# board2-d.net
KiCad netlist of a schematic drawn in EAGLE
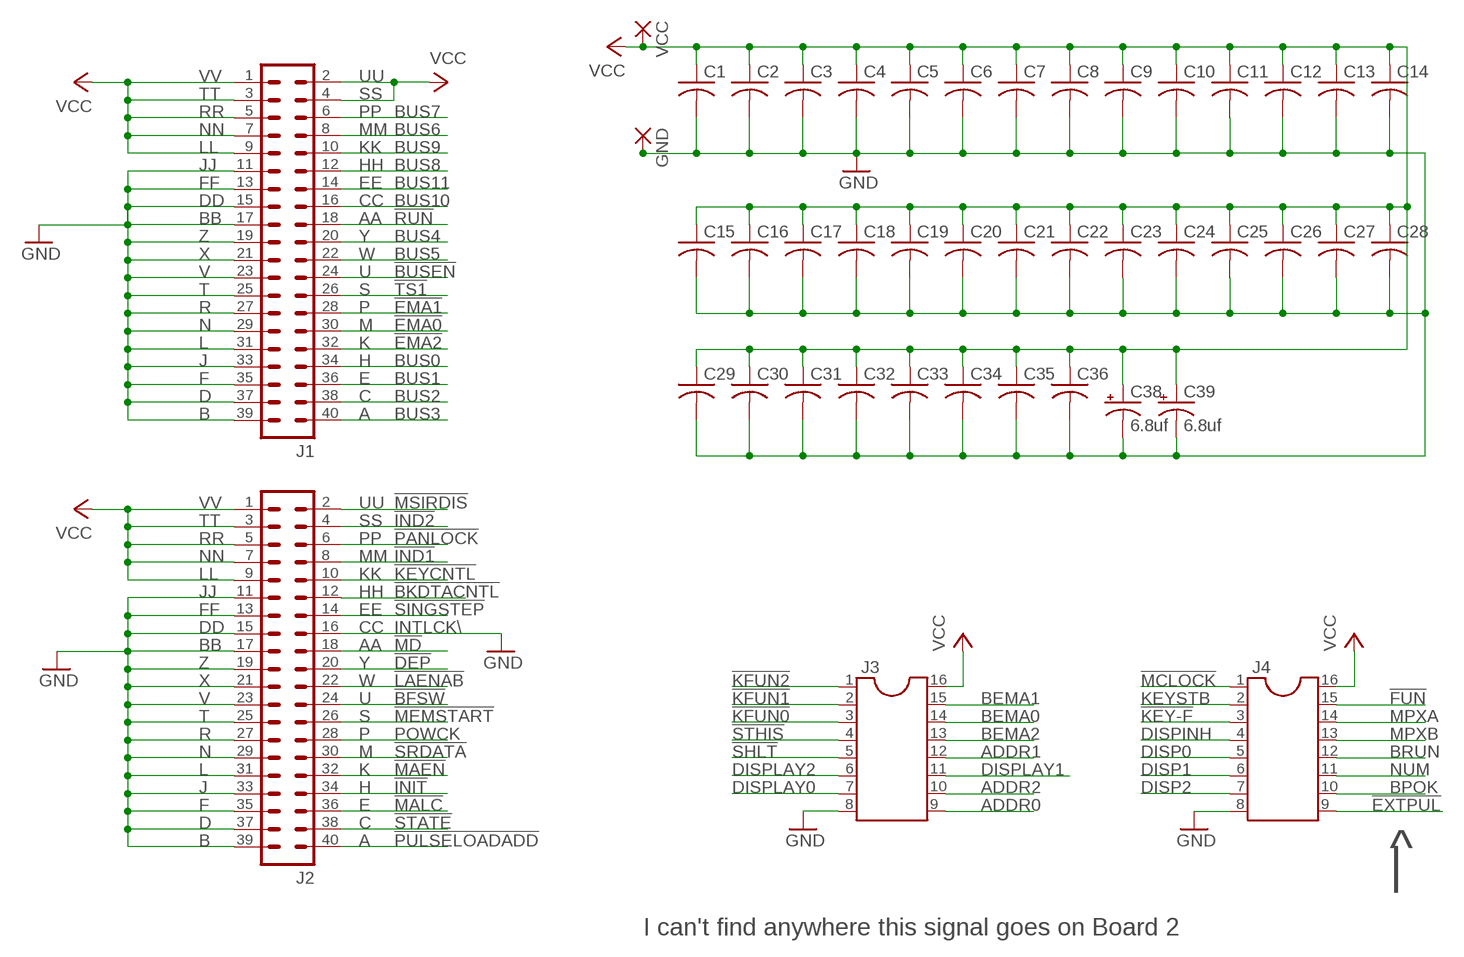
[diagram p0: schematic, sheet 1]
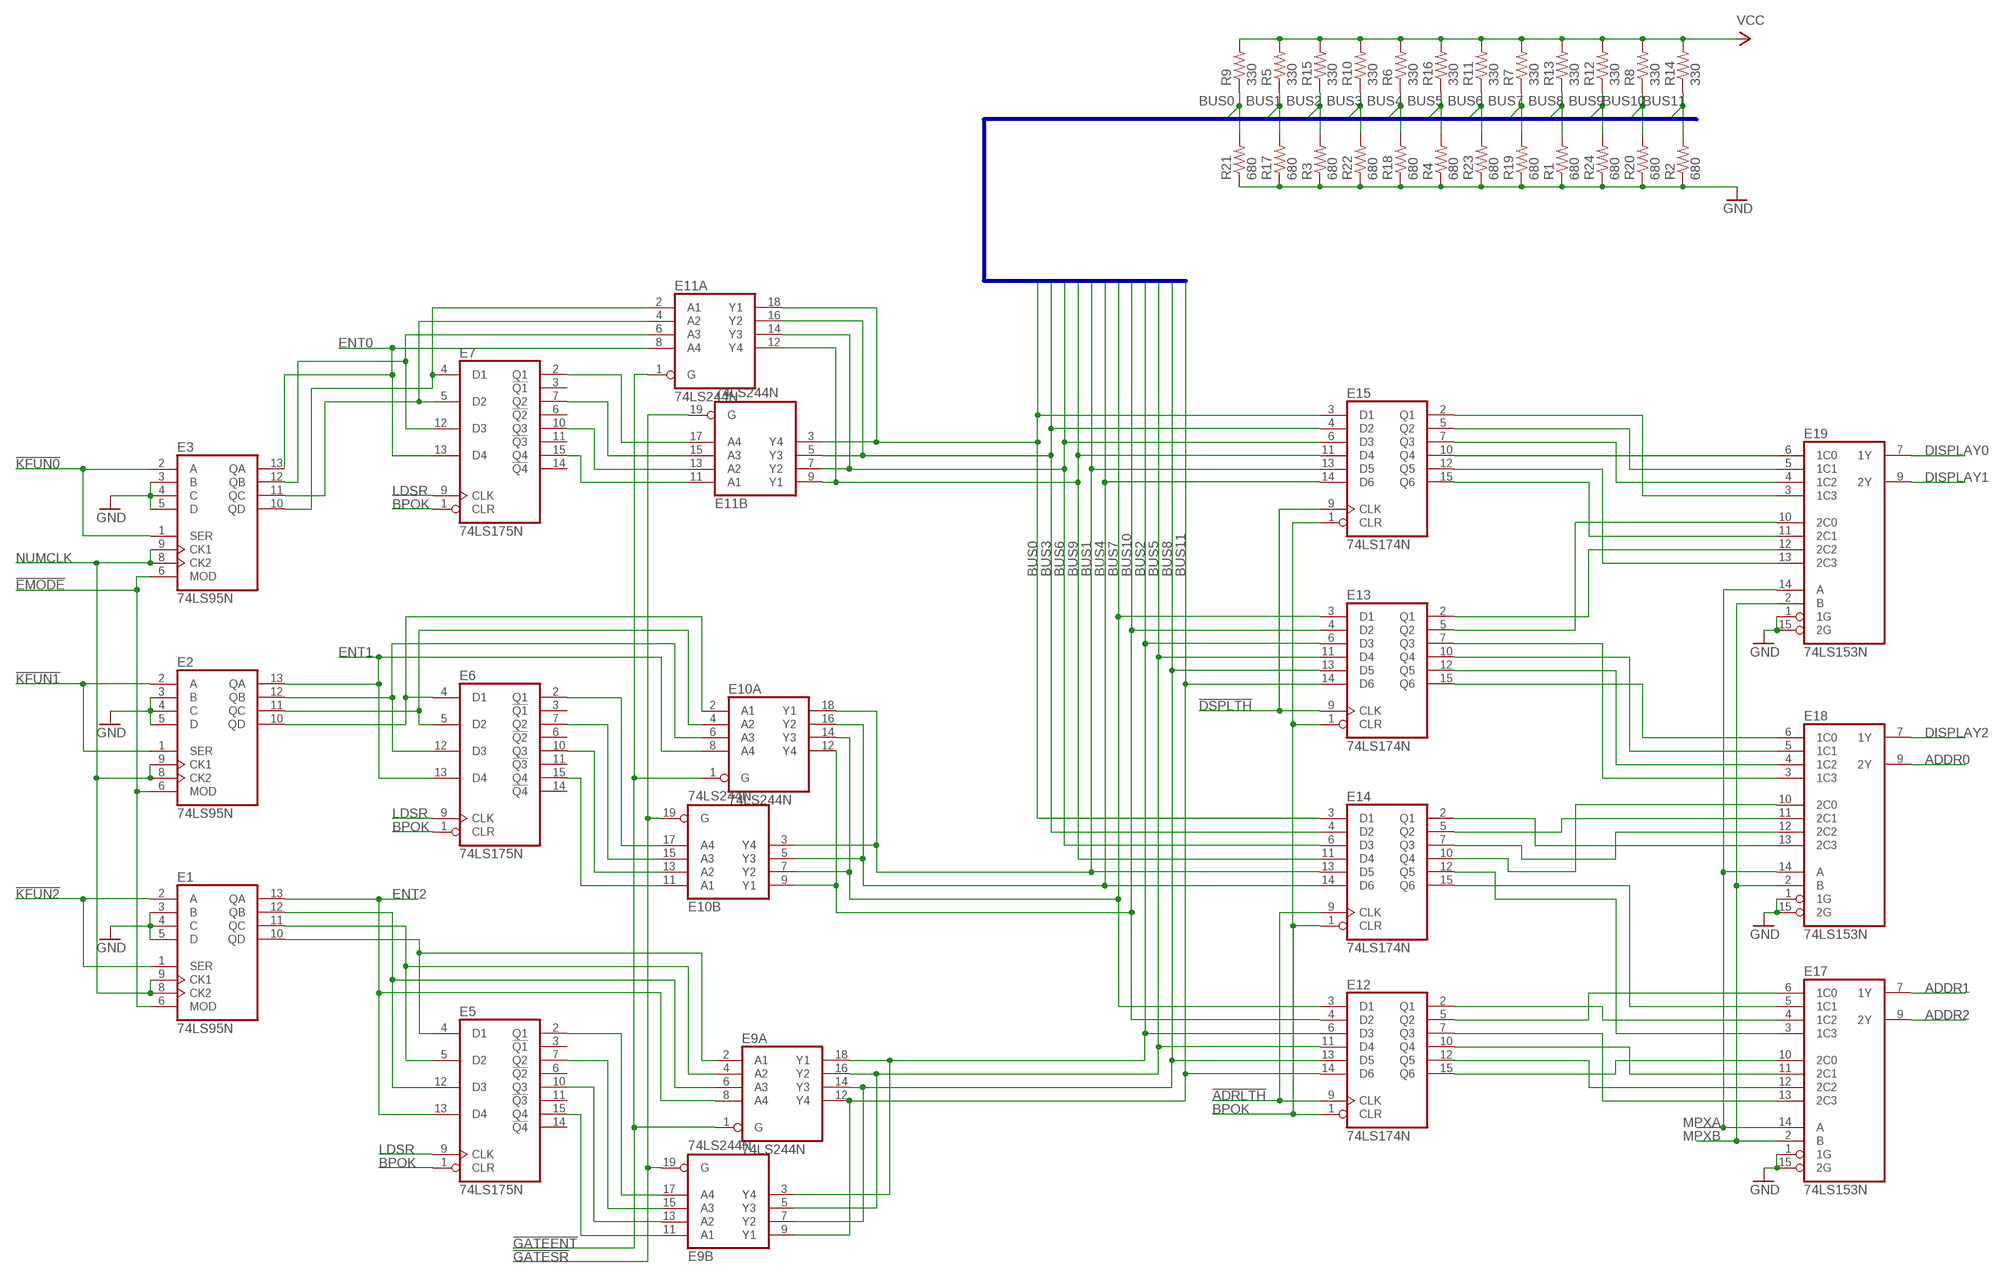
[diagram p1: schematic, sheet 2]
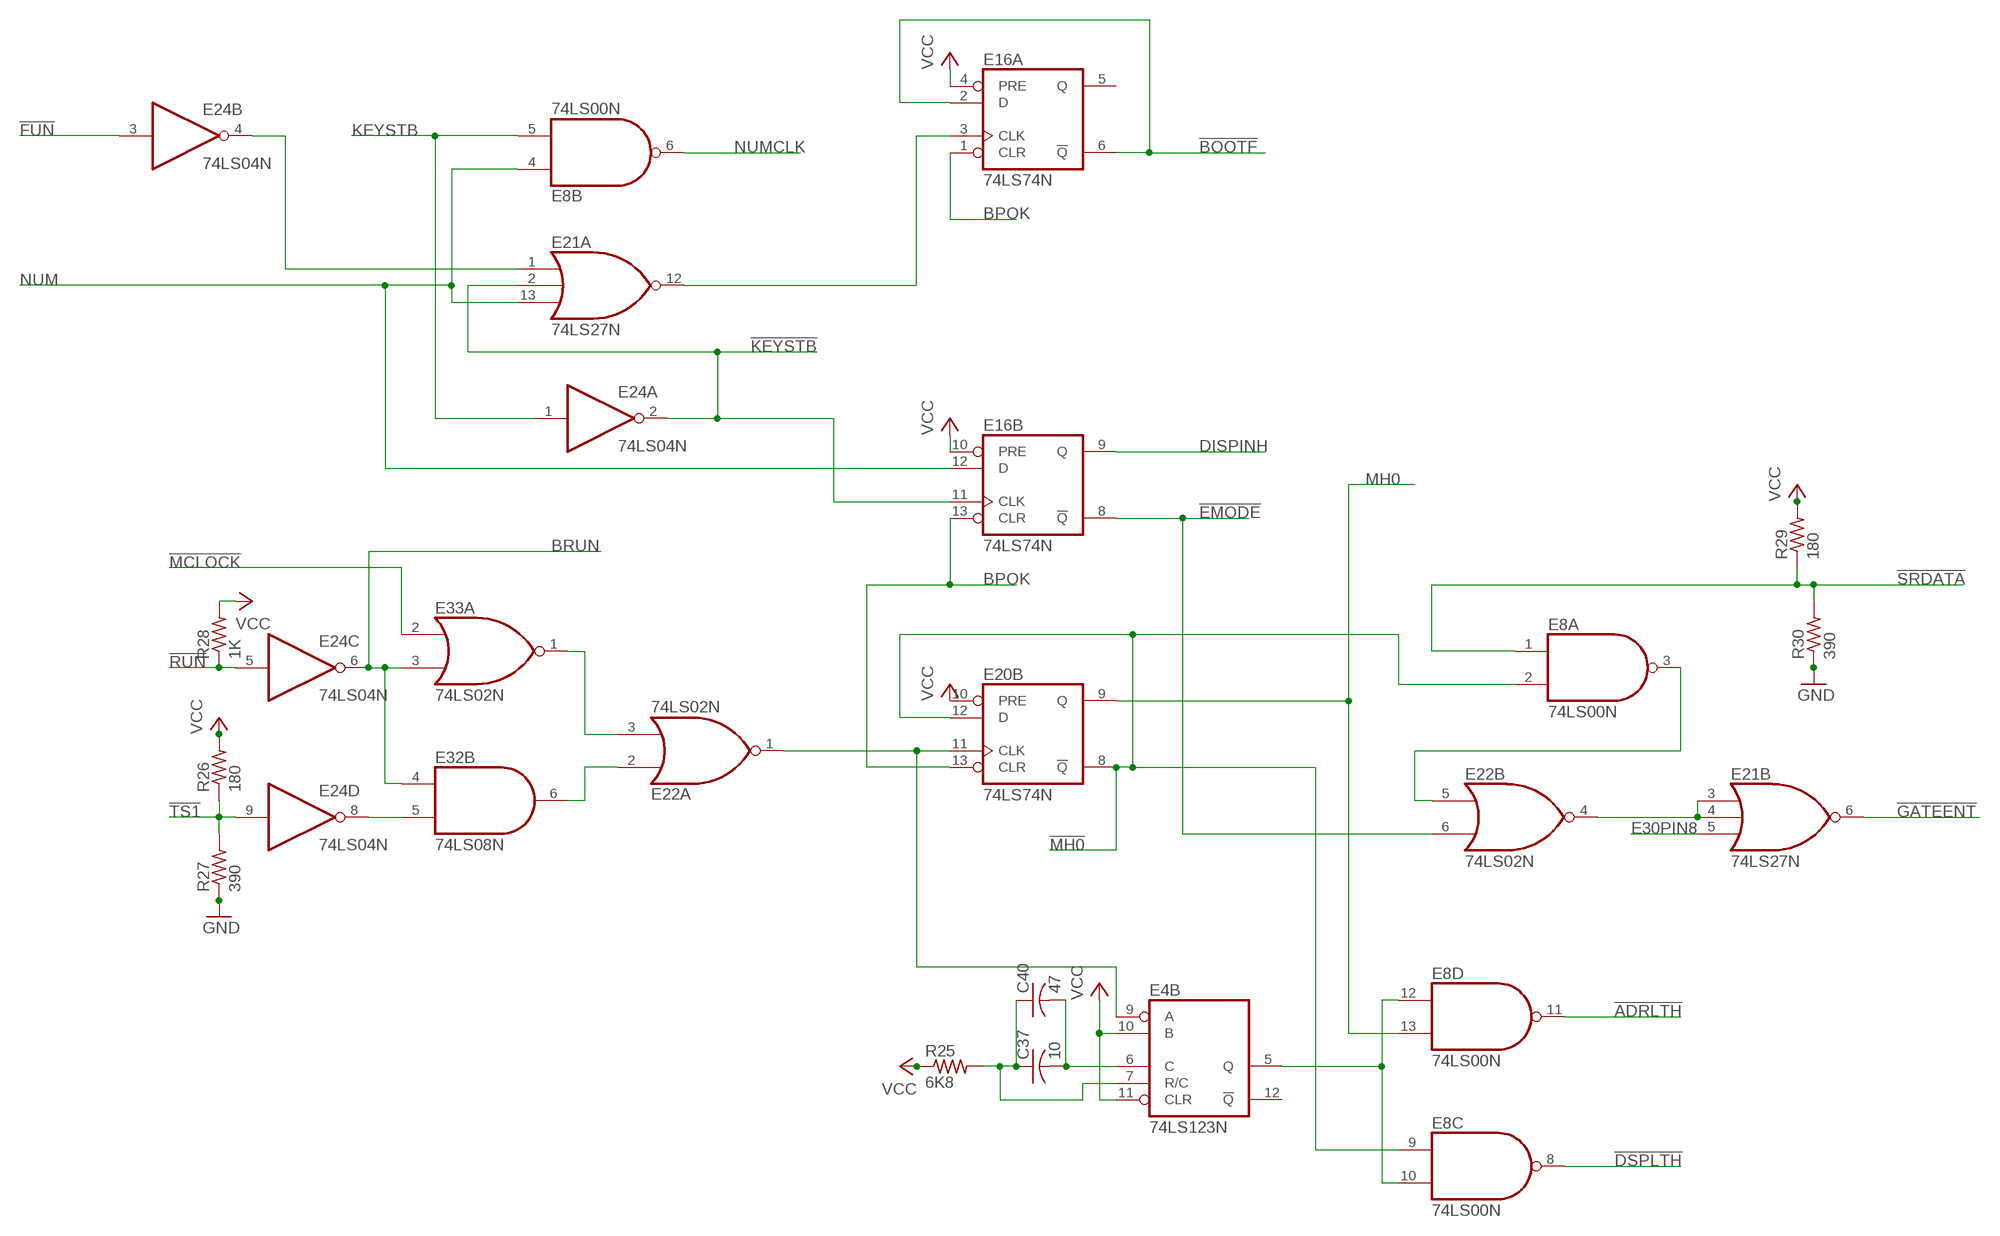
[diagram p2: schematic, sheet 3]
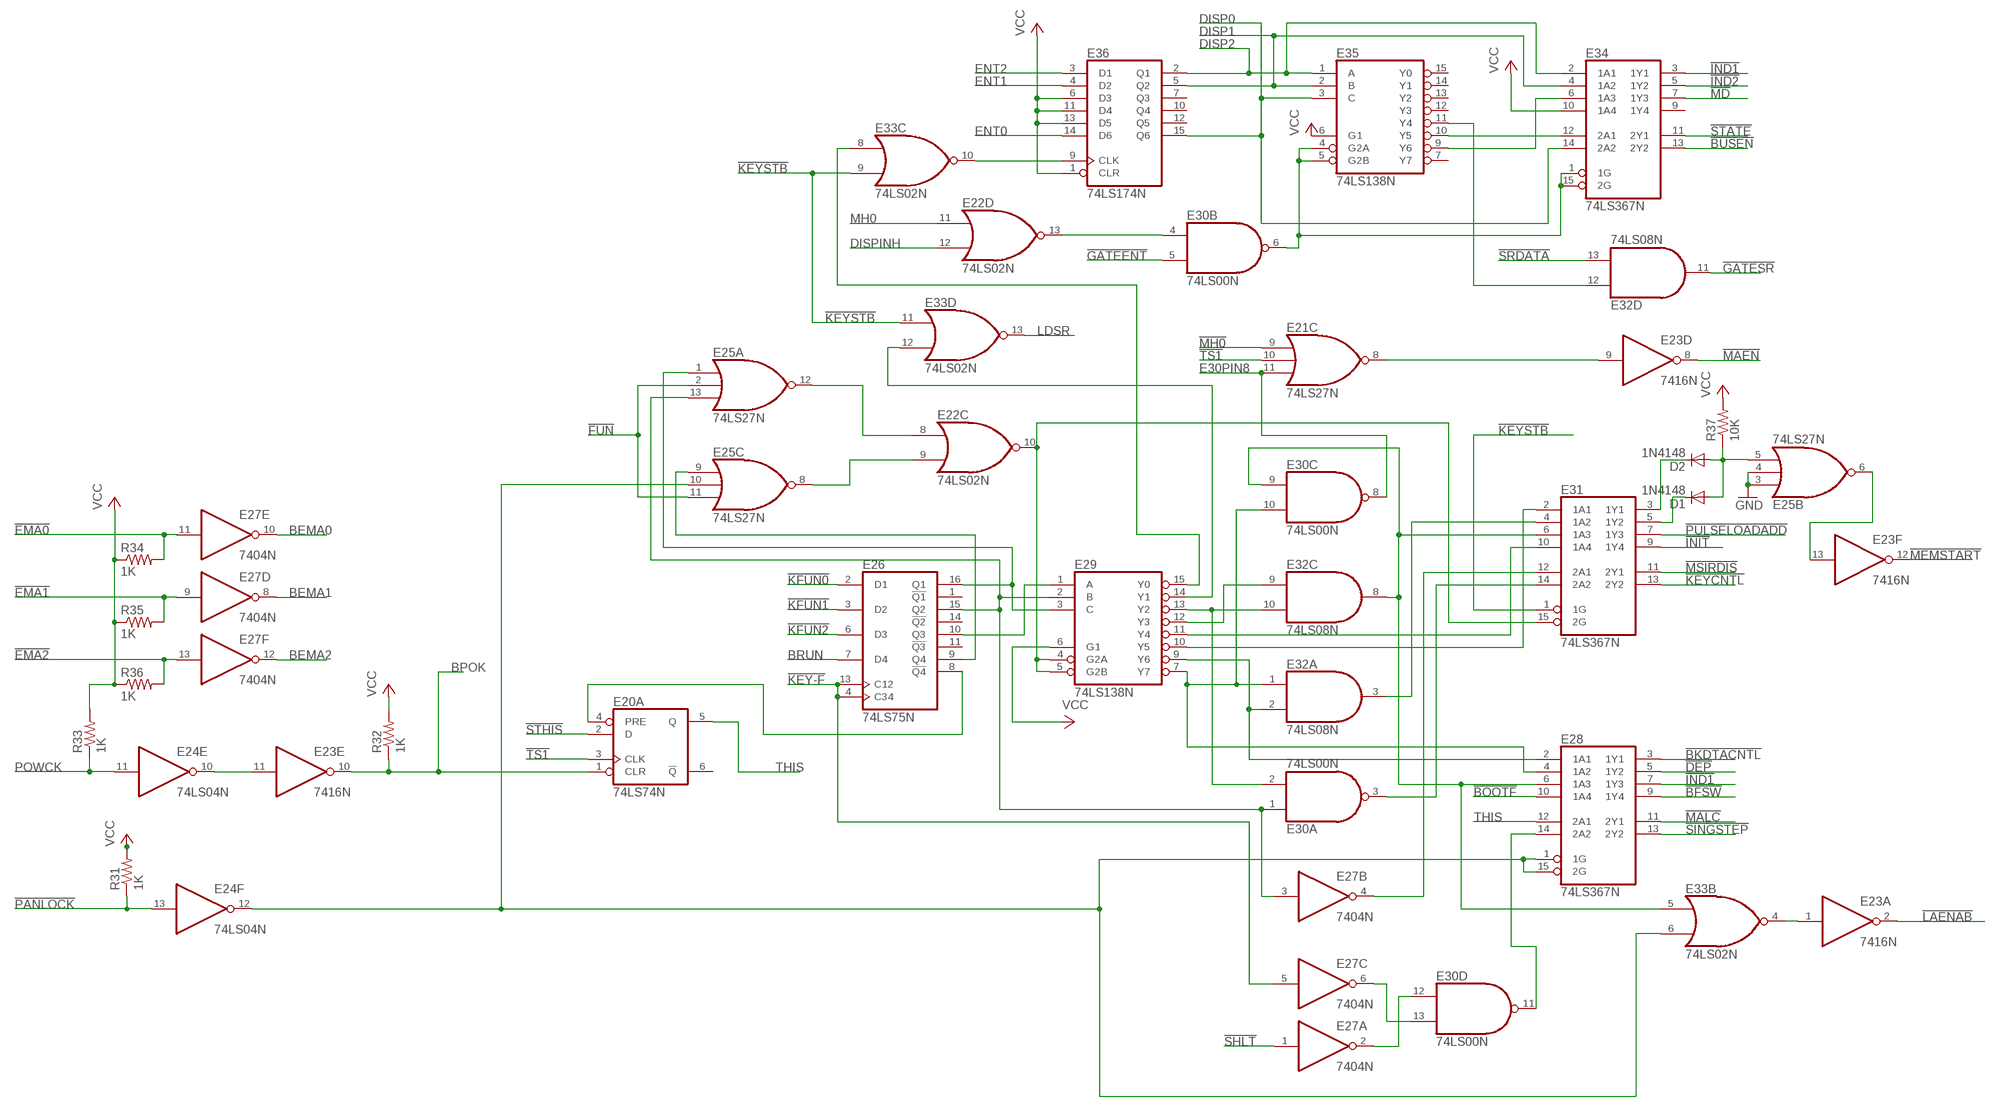
[diagram p3: schematic, sheet 4]

(export (version "E")
  (design (tool "Eeschema 10.0.6"))
  (components
    (comp (ref "E1")
      (value "74LS95N")
      (footprint "eagle-import:DIL14")
      (libsource (lib "eagle-import") (part "7495NLS"))
    )
    (comp (ref "E2")
      (value "74LS95N")
      (footprint "eagle-import:DIL14")
      (libsource (lib "eagle-import") (part "7495NLS"))
    )
    (comp (ref "E3")
      (value "74LS95N")
      (footprint "eagle-import:DIL14")
      (libsource (lib "eagle-import") (part "7495NLS"))
    )
    (comp (ref "E5")
      (value "74LS175N")
      (footprint "eagle-import:DIL16")
      (libsource (lib "eagle-import") (part "74175NLS"))
    )
    (comp (ref "E6")
      (value "74LS175N")
      (footprint "eagle-import:DIL16")
      (libsource (lib "eagle-import") (part "74175NLS"))
    )
    (comp (ref "E7")
      (value "74LS175N")
      (footprint "eagle-import:DIL16")
      (libsource (lib "eagle-import") (part "74175NLS"))
    )
    (comp (ref "E9")
      (value "74LS244N")
      (footprint "eagle-import:DIL20")
      (libsource (lib "eagle-import") (part "74244NS"))
    )
    (comp (ref "E10")
      (value "74LS244N")
      (footprint "eagle-import:DIL20")
      (libsource (lib "eagle-import") (part "74244NS"))
    )
    (comp (ref "E11")
      (value "74LS244N")
      (footprint "eagle-import:DIL20")
      (libsource (lib "eagle-import") (part "74244NS"))
    )
    (comp (ref "E12")
      (value "74LS174N")
      (footprint "eagle-import:DIL16")
      (libsource (lib "eagle-import") (part "74174NLS"))
    )
    (comp (ref "E13")
      (value "74LS174N")
      (footprint "eagle-import:DIL16")
      (libsource (lib "eagle-import") (part "74174NLS"))
    )
    (comp (ref "E14")
      (value "74LS174N")
      (footprint "eagle-import:DIL16")
      (libsource (lib "eagle-import") (part "74174NLS"))
    )
    (comp (ref "E15")
      (value "74LS174N")
      (footprint "eagle-import:DIL16")
      (libsource (lib "eagle-import") (part "74174NLS"))
    )
    (comp (ref "E17")
      (value "74LS153N")
      (footprint "eagle-import:DIL16")
      (libsource (lib "eagle-import") (part "74153NLS"))
    )
    (comp (ref "E18")
      (value "74LS153N")
      (footprint "eagle-import:DIL16")
      (libsource (lib "eagle-import") (part "74153NLS"))
    )
    (comp (ref "E19")
      (value "74LS153N")
      (footprint "eagle-import:DIL16")
      (libsource (lib "eagle-import") (part "74153NLS"))
    )
    (comp (ref "R1")
      (value "680")
      (footprint "eagle-import:0207_10")
      (libsource (lib "eagle-import") (part "R-US_0207/10"))
    )
    (comp (ref "R2")
      (value "680")
      (footprint "eagle-import:0207_10")
      (libsource (lib "eagle-import") (part "R-US_0207/10"))
    )
    (comp (ref "R3")
      (value "680")
      (footprint "eagle-import:0207_10")
      (libsource (lib "eagle-import") (part "R-US_0207/10"))
    )
    (comp (ref "R4")
      (value "680")
      (footprint "eagle-import:0207_10")
      (libsource (lib "eagle-import") (part "R-US_0207/10"))
    )
    (comp (ref "R5")
      (value "330")
      (footprint "eagle-import:0207_10")
      (libsource (lib "eagle-import") (part "R-US_0207/10"))
    )
    (comp (ref "R6")
      (value "330")
      (footprint "eagle-import:0207_10")
      (libsource (lib "eagle-import") (part "R-US_0207/10"))
    )
    (comp (ref "R7")
      (value "330")
      (footprint "eagle-import:0207_10")
      (libsource (lib "eagle-import") (part "R-US_0207/10"))
    )
    (comp (ref "R8")
      (value "330")
      (footprint "eagle-import:0207_10")
      (libsource (lib "eagle-import") (part "R-US_0207/10"))
    )
    (comp (ref "R9")
      (value "330")
      (footprint "eagle-import:0207_10")
      (libsource (lib "eagle-import") (part "R-US_0207/10"))
    )
    (comp (ref "R10")
      (value "330")
      (footprint "eagle-import:0207_10")
      (libsource (lib "eagle-import") (part "R-US_0207/10"))
    )
    (comp (ref "R11")
      (value "330")
      (footprint "eagle-import:0207_10")
      (libsource (lib "eagle-import") (part "R-US_0207/10"))
    )
    (comp (ref "R12")
      (value "330")
      (footprint "eagle-import:0207_10")
      (libsource (lib "eagle-import") (part "R-US_0207/10"))
    )
    (comp (ref "R13")
      (value "330")
      (footprint "eagle-import:0207_10")
      (libsource (lib "eagle-import") (part "R-US_0207/10"))
    )
    (comp (ref "R14")
      (value "330")
      (footprint "eagle-import:0207_10")
      (libsource (lib "eagle-import") (part "R-US_0207/10"))
    )
    (comp (ref "R15")
      (value "330")
      (footprint "eagle-import:0207_10")
      (libsource (lib "eagle-import") (part "R-US_0207/10"))
    )
    (comp (ref "R16")
      (value "330")
      (footprint "eagle-import:0207_10")
      (libsource (lib "eagle-import") (part "R-US_0207/10"))
    )
    (comp (ref "R17")
      (value "680")
      (footprint "eagle-import:0207_10")
      (libsource (lib "eagle-import") (part "R-US_0207/10"))
    )
    (comp (ref "R18")
      (value "680")
      (footprint "eagle-import:0207_10")
      (libsource (lib "eagle-import") (part "R-US_0207/10"))
    )
    (comp (ref "R19")
      (value "680")
      (footprint "eagle-import:0207_10")
      (libsource (lib "eagle-import") (part "R-US_0207/10"))
    )
    (comp (ref "R20")
      (value "680")
      (footprint "eagle-import:0207_10")
      (libsource (lib "eagle-import") (part "R-US_0207/10"))
    )
    (comp (ref "R21")
      (value "680")
      (footprint "eagle-import:0207_10")
      (libsource (lib "eagle-import") (part "R-US_0207/10"))
    )
    (comp (ref "R22")
      (value "680")
      (footprint "eagle-import:0207_10")
      (libsource (lib "eagle-import") (part "R-US_0207/10"))
    )
    (comp (ref "R23")
      (value "680")
      (footprint "eagle-import:0207_10")
      (libsource (lib "eagle-import") (part "R-US_0207/10"))
    )
    (comp (ref "R24")
      (value "680")
      (footprint "eagle-import:0207_10")
      (libsource (lib "eagle-import") (part "R-US_0207/10"))
    )
    (comp (ref "D1")
      (value "1N4148")
      (footprint "eagle-import:DO35-10")
      (libsource (lib "eagle-import") (part "1N4148"))
    )
    (comp (ref "D2")
      (value "1N4148")
      (footprint "eagle-import:DO35-10")
      (libsource (lib "eagle-import") (part "1N4148"))
    )
    (comp (ref "E20")
      (value "74LS74N")
      (footprint "eagle-import:DIL14")
      (libsource (lib "eagle-import") (part "7474NLS"))
    )
    (comp (ref "E21")
      (value "74LS27N")
      (footprint "eagle-import:DIL14")
      (libsource (lib "eagle-import") (part "7427NLS"))
    )
    (comp (ref "E22")
      (value "74LS02N")
      (footprint "eagle-import:DIL14")
      (libsource (lib "eagle-import") (part "7402NLS"))
    )
    (comp (ref "E23")
      (value "7416N")
      (footprint "eagle-import:DIL14")
      (libsource (lib "eagle-import") (part "7416N"))
    )
    (comp (ref "E24")
      (value "74LS04N")
      (footprint "eagle-import:DIL14")
      (libsource (lib "eagle-import") (part "7404NLS"))
    )
    (comp (ref "E25")
      (value "74LS27N")
      (footprint "eagle-import:DIL14")
      (libsource (lib "eagle-import") (part "7427NLS"))
    )
    (comp (ref "E26")
      (value "74LS75N")
      (footprint "eagle-import:DIL16")
      (libsource (lib "eagle-import") (part "7475NLS"))
    )
    (comp (ref "E27")
      (value "7404N")
      (footprint "eagle-import:DIL14")
      (libsource (lib "eagle-import") (part "7404N"))
    )
    (comp (ref "E28")
      (value "74LS367N")
      (footprint "eagle-import:DIL16")
      (libsource (lib "eagle-import") (part "74367N"))
    )
    (comp (ref "E29")
      (value "74LS138N")
      (footprint "eagle-import:DIL16")
      (libsource (lib "eagle-import") (part "74138NLS"))
    )
    (comp (ref "E30")
      (value "74LS00N")
      (footprint "eagle-import:DIL14")
      (libsource (lib "eagle-import") (part "7400NLS"))
    )
    (comp (ref "E31")
      (value "74LS367N")
      (footprint "eagle-import:DIL16")
      (libsource (lib "eagle-import") (part "74367N"))
    )
    (comp (ref "E32")
      (value "74LS08N")
      (footprint "eagle-import:DIL14")
      (libsource (lib "eagle-import") (part "7408NLS"))
    )
    (comp (ref "E33")
      (value "74LS02N")
      (footprint "eagle-import:DIL14")
      (libsource (lib "eagle-import") (part "7402NLS"))
    )
    (comp (ref "E34")
      (value "74LS367N")
      (footprint "eagle-import:DIL16")
      (libsource (lib "eagle-import") (part "74367N"))
    )
    (comp (ref "E35")
      (value "74LS138N")
      (footprint "eagle-import:DIL16")
      (libsource (lib "eagle-import") (part "74138NLS"))
    )
    (comp (ref "E36")
      (value "74LS174N")
      (footprint "eagle-import:DIL16")
      (libsource (lib "eagle-import") (part "74174NLS"))
    )
    (comp (ref "R31")
      (value "1K")
      (footprint "eagle-import:0207_10")
      (libsource (lib "eagle-import") (part "R-US_0207/10"))
    )
    (comp (ref "R32")
      (value "1K")
      (footprint "eagle-import:0207_10")
      (libsource (lib "eagle-import") (part "R-US_0207/10"))
    )
    (comp (ref "R33")
      (value "1K")
      (footprint "eagle-import:0207_10")
      (libsource (lib "eagle-import") (part "R-US_0207/10"))
    )
    (comp (ref "R34")
      (value "1K")
      (footprint "eagle-import:0207_10")
      (libsource (lib "eagle-import") (part "R-US_0207/10"))
    )
    (comp (ref "R35")
      (value "1K")
      (footprint "eagle-import:0207_10")
      (libsource (lib "eagle-import") (part "R-US_0207/10"))
    )
    (comp (ref "R36")
      (value "1K")
      (footprint "eagle-import:0207_10")
      (libsource (lib "eagle-import") (part "R-US_0207/10"))
    )
    (comp (ref "R37")
      (value "10K")
      (footprint "eagle-import:0207_10")
      (libsource (lib "eagle-import") (part "R-US_0207/10"))
    )
    (comp (ref "C1")
      (value "C-US050-025X075")
      (footprint "eagle-import:C050-025X075")
      (libsource (lib "eagle-import") (part "C-US050-025X075"))
    )
    (comp (ref "C2")
      (value "C-US050-025X075")
      (footprint "eagle-import:C050-025X075")
      (libsource (lib "eagle-import") (part "C-US050-025X075"))
    )
    (comp (ref "C3")
      (value "C-US050-025X075")
      (footprint "eagle-import:C050-025X075")
      (libsource (lib "eagle-import") (part "C-US050-025X075"))
    )
    (comp (ref "C4")
      (value "C-US050-025X075")
      (footprint "eagle-import:C050-025X075")
      (libsource (lib "eagle-import") (part "C-US050-025X075"))
    )
    (comp (ref "C5")
      (value "C-US050-025X075")
      (footprint "eagle-import:C050-025X075")
      (libsource (lib "eagle-import") (part "C-US050-025X075"))
    )
    (comp (ref "C6")
      (value "C-US050-025X075")
      (footprint "eagle-import:C050-025X075")
      (libsource (lib "eagle-import") (part "C-US050-025X075"))
    )
    (comp (ref "C7")
      (value "C-US050-025X075")
      (footprint "eagle-import:C050-025X075")
      (libsource (lib "eagle-import") (part "C-US050-025X075"))
    )
    (comp (ref "C8")
      (value "C-US050-025X075")
      (footprint "eagle-import:C050-025X075")
      (libsource (lib "eagle-import") (part "C-US050-025X075"))
    )
    (comp (ref "C9")
      (value "C-US050-025X075")
      (footprint "eagle-import:C050-025X075")
      (libsource (lib "eagle-import") (part "C-US050-025X075"))
    )
    (comp (ref "C10")
      (value "C-US050-025X075")
      (footprint "eagle-import:C050-025X075")
      (libsource (lib "eagle-import") (part "C-US050-025X075"))
    )
    (comp (ref "C11")
      (value "C-US050-025X075")
      (footprint "eagle-import:C050-025X075")
      (libsource (lib "eagle-import") (part "C-US050-025X075"))
    )
    (comp (ref "C12")
      (value "C-US050-025X075")
      (footprint "eagle-import:C050-025X075")
      (libsource (lib "eagle-import") (part "C-US050-025X075"))
    )
    (comp (ref "C13")
      (value "C-US050-025X075")
      (footprint "eagle-import:C050-025X075")
      (libsource (lib "eagle-import") (part "C-US050-025X075"))
    )
    (comp (ref "C14")
      (value "C-US050-025X075")
      (footprint "eagle-import:C050-025X075")
      (libsource (lib "eagle-import") (part "C-US050-025X075"))
    )
    (comp (ref "C15")
      (value "C-US050-025X075")
      (footprint "eagle-import:C050-025X075")
      (libsource (lib "eagle-import") (part "C-US050-025X075"))
    )
    (comp (ref "C16")
      (value "C-US050-025X075")
      (footprint "eagle-import:C050-025X075")
      (libsource (lib "eagle-import") (part "C-US050-025X075"))
    )
    (comp (ref "C17")
      (value "C-US050-025X075")
      (footprint "eagle-import:C050-025X075")
      (libsource (lib "eagle-import") (part "C-US050-025X075"))
    )
    (comp (ref "C18")
      (value "C-US050-025X075")
      (footprint "eagle-import:C050-025X075")
      (libsource (lib "eagle-import") (part "C-US050-025X075"))
    )
    (comp (ref "C19")
      (value "C-US050-025X075")
      (footprint "eagle-import:C050-025X075")
      (libsource (lib "eagle-import") (part "C-US050-025X075"))
    )
    (comp (ref "C20")
      (value "C-US050-025X075")
      (footprint "eagle-import:C050-025X075")
      (libsource (lib "eagle-import") (part "C-US050-025X075"))
    )
    (comp (ref "C21")
      (value "C-US050-025X075")
      (footprint "eagle-import:C050-025X075")
      (libsource (lib "eagle-import") (part "C-US050-025X075"))
    )
    (comp (ref "C22")
      (value "C-US050-025X075")
      (footprint "eagle-import:C050-025X075")
      (libsource (lib "eagle-import") (part "C-US050-025X075"))
    )
    (comp (ref "C23")
      (value "C-US050-025X075")
      (footprint "eagle-import:C050-025X075")
      (libsource (lib "eagle-import") (part "C-US050-025X075"))
    )
    (comp (ref "C24")
      (value "C-US050-025X075")
      (footprint "eagle-import:C050-025X075")
      (libsource (lib "eagle-import") (part "C-US050-025X075"))
    )
    (comp (ref "C25")
      (value "C-US050-025X075")
      (footprint "eagle-import:C050-025X075")
      (libsource (lib "eagle-import") (part "C-US050-025X075"))
    )
    (comp (ref "C26")
      (value "C-US050-025X075")
      (footprint "eagle-import:C050-025X075")
      (libsource (lib "eagle-import") (part "C-US050-025X075"))
    )
    (comp (ref "C27")
      (value "C-US050-025X075")
      (footprint "eagle-import:C050-025X075")
      (libsource (lib "eagle-import") (part "C-US050-025X075"))
    )
    (comp (ref "C28")
      (value "C-US050-025X075")
      (footprint "eagle-import:C050-025X075")
      (libsource (lib "eagle-import") (part "C-US050-025X075"))
    )
    (comp (ref "C29")
      (value "C-US050-025X075")
      (footprint "eagle-import:C050-025X075")
      (libsource (lib "eagle-import") (part "C-US050-025X075"))
    )
    (comp (ref "C30")
      (value "C-US050-025X075")
      (footprint "eagle-import:C050-025X075")
      (libsource (lib "eagle-import") (part "C-US050-025X075"))
    )
    (comp (ref "C31")
      (value "C-US050-025X075")
      (footprint "eagle-import:C050-025X075")
      (libsource (lib "eagle-import") (part "C-US050-025X075"))
    )
    (comp (ref "C32")
      (value "C-US050-025X075")
      (footprint "eagle-import:C050-025X075")
      (libsource (lib "eagle-import") (part "C-US050-025X075"))
    )
    (comp (ref "C33")
      (value "C-US050-025X075")
      (footprint "eagle-import:C050-025X075")
      (libsource (lib "eagle-import") (part "C-US050-025X075"))
    )
    (comp (ref "C34")
      (value "C-US050-025X075")
      (footprint "eagle-import:C050-025X075")
      (libsource (lib "eagle-import") (part "C-US050-025X075"))
    )
    (comp (ref "C35")
      (value "C-US050-025X075")
      (footprint "eagle-import:C050-025X075")
      (libsource (lib "eagle-import") (part "C-US050-025X075"))
    )
    (comp (ref "C36")
      (value "C-US050-025X075")
      (footprint "eagle-import:C050-025X075")
      (libsource (lib "eagle-import") (part "C-US050-025X075"))
    )
    (comp (ref "C38")
      (value "6.8uf")
      (footprint "eagle-import:E15-5")
      (libsource (lib "eagle-import") (part "CPOL-USE15-5AXIAL"))
    )
    (comp (ref "C39")
      (value "6.8uf")
      (footprint "eagle-import:E15-5")
      (libsource (lib "eagle-import") (part "CPOL-USE15-5AXIAL"))
    )
    (comp (ref "GND")
      (value "3,81/1,4")
      (footprint "eagle-import:3,81_1,4")
      (libsource (lib "eagle-import") (part "3,81/1,4"))
    )
    (comp (ref "J1")
      (value "40H")
      (footprint "eagle-import:40H")
      (libsource (lib "eagle-import") (part "40H"))
    )
    (comp (ref "J2")
      (value "40H")
      (footprint "eagle-import:40H")
      (libsource (lib "eagle-import") (part "40H"))
    )
    (comp (ref "J3")
      (value "DIL16S")
      (footprint "eagle-import:SOCKED-16")
      (libsource (lib "eagle-import") (part "DIL16S"))
    )
    (comp (ref "J4")
      (value "DIL16S")
      (footprint "eagle-import:SOCKED-16")
      (libsource (lib "eagle-import") (part "DIL16S"))
    )
    (comp (ref "VCC")
      (value "3,81/1,4")
      (footprint "eagle-import:3,81_1,4")
      (libsource (lib "eagle-import") (part "3,81/1,4"))
    )
    (comp (ref "C37")
      (value "10")
      (footprint "eagle-import:C050-025X075")
      (libsource (lib "eagle-import") (part "C-US050-025X075"))
    )
    (comp (ref "C40")
      (value "47")
      (footprint "eagle-import:C050-025X075")
      (libsource (lib "eagle-import") (part "C-US050-025X075"))
    )
    (comp (ref "E4")
      (value "74LS123N")
      (footprint "eagle-import:DIL16")
      (libsource (lib "eagle-import") (part "74123NLS"))
    )
    (comp (ref "E8")
      (value "74LS00N")
      (footprint "eagle-import:DIL14")
      (libsource (lib "eagle-import") (part "7400NLS"))
    )
    (comp (ref "E16")
      (value "74LS74N")
      (footprint "eagle-import:DIL14")
      (libsource (lib "eagle-import") (part "7474NLS"))
    )
    (comp (ref "R25")
      (value "6K8")
      (footprint "eagle-import:0207_10")
      (libsource (lib "eagle-import") (part "R-US_0207/10"))
    )
    (comp (ref "R26")
      (value "180")
      (footprint "eagle-import:0207_10")
      (libsource (lib "eagle-import") (part "R-US_0207/10"))
    )
    (comp (ref "R27")
      (value "390")
      (footprint "eagle-import:0207_10")
      (libsource (lib "eagle-import") (part "R-US_0207/10"))
    )
    (comp (ref "R28")
      (value "1K")
      (footprint "eagle-import:0207_10")
      (libsource (lib "eagle-import") (part "R-US_0207/10"))
    )
    (comp (ref "R29")
      (value "180")
      (footprint "eagle-import:0207_10")
      (libsource (lib "eagle-import") (part "R-US_0207/10"))
    )
    (comp (ref "R30")
      (value "390")
      (footprint "eagle-import:0207_10")
      (libsource (lib "eagle-import") (part "R-US_0207/10"))
    )
  )
  (nets
    (net (code "1") (name "ADDR0") (class "Default")
      (node (ref "E18") (pin "9") (pinfunction "2Y_9") (pintype "output"))
      (node (ref "J3") (pin "9") (pinfunction "9_9") (pintype "passive"))
    )
    (net (code "2") (name "ADDR1") (class "Default")
      (node (ref "E17") (pin "7") (pinfunction "1Y_7") (pintype "output"))
      (node (ref "J3") (pin "12") (pinfunction "12_12") (pintype "passive"))
    )
    (net (code "3") (name "ADDR2") (class "Default")
      (node (ref "E17") (pin "9") (pinfunction "2Y_9") (pintype "output"))
      (node (ref "J3") (pin "10") (pinfunction "10_10") (pintype "passive"))
    )
    (net (code "4") (name "BEMA0") (class "Default")
      (node (ref "E27") (pin "10") (pinfunction "O_10") (pintype "output"))
      (node (ref "J3") (pin "14") (pinfunction "14_14") (pintype "passive"))
    )
    (net (code "5") (name "BEMA1") (class "Default")
      (node (ref "E27") (pin "8") (pinfunction "O_8") (pintype "output"))
      (node (ref "J3") (pin "15") (pinfunction "15_15") (pintype "passive"))
    )
    (net (code "6") (name "BEMA2") (class "Default")
      (node (ref "E27") (pin "12") (pinfunction "O_12") (pintype "output"))
      (node (ref "J3") (pin "13") (pinfunction "13_13") (pintype "passive"))
    )
    (net (code "7") (name "BPOK") (class "Default")
      (node (ref "E12") (pin "1") (pinfunction "CLR_1") (pintype "input"))
      (node (ref "E13") (pin "1") (pinfunction "CLR_1") (pintype "input"))
      (node (ref "E14") (pin "1") (pinfunction "CLR_1") (pintype "input"))
      (node (ref "E15") (pin "1") (pinfunction "CLR_1") (pintype "input"))
      (node (ref "E16") (pin "1") (pinfunction "CLR_1") (pintype "input"))
      (node (ref "E16") (pin "13") (pinfunction "CLR_13") (pintype "input"))
      (node (ref "E20") (pin "1") (pinfunction "CLR_1") (pintype "input"))
      (node (ref "E20") (pin "13") (pinfunction "CLR_13") (pintype "input"))
      (node (ref "E23") (pin "10") (pinfunction "O_10") (pintype "open_collector"))
      (node (ref "E5") (pin "1") (pinfunction "CLR_1") (pintype "input"))
      (node (ref "E6") (pin "1") (pinfunction "CLR_1") (pintype "input"))
      (node (ref "E7") (pin "1") (pinfunction "CLR_1") (pintype "input"))
      (node (ref "J4") (pin "10") (pinfunction "10_10") (pintype "passive"))
      (node (ref "R32") (pin "1") (pinfunction "1_1") (pintype "passive"))
    )
    (net (code "8") (name "BRUN") (class "Default")
      (node (ref "E24") (pin "6") (pinfunction "O_6") (pintype "output"))
      (node (ref "E26") (pin "7") (pinfunction "D4_7") (pintype "input"))
      (node (ref "E32") (pin "4") (pinfunction "I0_4") (pintype "input"))
      (node (ref "E33") (pin "3") (pinfunction "I1_3") (pintype "input"))
      (node (ref "J4") (pin "12") (pinfunction "12_12") (pintype "passive"))
    )
    (net (code "9") (name "BUS0") (class "Default")
      (node (ref "E11") (pin "18") (pinfunction "Y1_18") (pintype "tri_state"))
      (node (ref "E11") (pin "3") (pinfunction "Y4_3") (pintype "tri_state"))
      (node (ref "E14") (pin "3") (pinfunction "D1_3") (pintype "input"))
      (node (ref "E15") (pin "3") (pinfunction "D1_3") (pintype "input"))
      (node (ref "J1") (pin "34") (pinfunction "34_34") (pintype "passive"))
      (node (ref "R21") (pin "2") (pinfunction "2_2") (pintype "passive"))
      (node (ref "R9") (pin "1") (pinfunction "1_1") (pintype "passive"))
    )
    (net (code "10") (name "BUS1") (class "Default")
      (node (ref "E10") (pin "18") (pinfunction "Y1_18") (pintype "tri_state"))
      (node (ref "E10") (pin "3") (pinfunction "Y4_3") (pintype "tri_state"))
      (node (ref "E14") (pin "13") (pinfunction "D5_13") (pintype "input"))
      (node (ref "E15") (pin "13") (pinfunction "D5_13") (pintype "input"))
      (node (ref "J1") (pin "36") (pinfunction "36_36") (pintype "passive"))
      (node (ref "R17") (pin "2") (pinfunction "2_2") (pintype "passive"))
      (node (ref "R5") (pin "1") (pinfunction "1_1") (pintype "passive"))
    )
    (net (code "11") (name "BUS2") (class "Default")
      (node (ref "E12") (pin "6") (pinfunction "D3_6") (pintype "input"))
      (node (ref "E13") (pin "6") (pinfunction "D3_6") (pintype "input"))
      (node (ref "E9") (pin "18") (pinfunction "Y1_18") (pintype "tri_state"))
      (node (ref "E9") (pin "3") (pinfunction "Y4_3") (pintype "tri_state"))
      (node (ref "J1") (pin "38") (pinfunction "38_38") (pintype "passive"))
      (node (ref "R15") (pin "1") (pinfunction "1_1") (pintype "passive"))
      (node (ref "R3") (pin "2") (pinfunction "2_2") (pintype "passive"))
    )
    (net (code "12") (name "BUS3") (class "Default")
      (node (ref "E11") (pin "16") (pinfunction "Y2_16") (pintype "tri_state"))
      (node (ref "E11") (pin "5") (pinfunction "Y3_5") (pintype "tri_state"))
      (node (ref "E14") (pin "4") (pinfunction "D2_4") (pintype "input"))
      (node (ref "E15") (pin "4") (pinfunction "D2_4") (pintype "input"))
      (node (ref "J1") (pin "40") (pinfunction "40_40") (pintype "passive"))
      (node (ref "R10") (pin "1") (pinfunction "1_1") (pintype "passive"))
      (node (ref "R22") (pin "2") (pinfunction "2_2") (pintype "passive"))
    )
    (net (code "13") (name "BUS4") (class "Default")
      (node (ref "E10") (pin "16") (pinfunction "Y2_16") (pintype "tri_state"))
      (node (ref "E10") (pin "5") (pinfunction "Y3_5") (pintype "tri_state"))
      (node (ref "E14") (pin "14") (pinfunction "D6_14") (pintype "input"))
      (node (ref "E15") (pin "14") (pinfunction "D6_14") (pintype "input"))
      (node (ref "J1") (pin "20") (pinfunction "20_20") (pintype "passive"))
      (node (ref "R18") (pin "2") (pinfunction "2_2") (pintype "passive"))
      (node (ref "R6") (pin "1") (pinfunction "1_1") (pintype "passive"))
    )
    (net (code "14") (name "BUS5") (class "Default")
      (node (ref "E12") (pin "11") (pinfunction "D4_11") (pintype "input"))
      (node (ref "E13") (pin "11") (pinfunction "D4_11") (pintype "input"))
      (node (ref "E9") (pin "16") (pinfunction "Y2_16") (pintype "tri_state"))
      (node (ref "E9") (pin "5") (pinfunction "Y3_5") (pintype "tri_state"))
      (node (ref "J1") (pin "22") (pinfunction "22_22") (pintype "passive"))
      (node (ref "R16") (pin "1") (pinfunction "1_1") (pintype "passive"))
      (node (ref "R4") (pin "2") (pinfunction "2_2") (pintype "passive"))
    )
    (net (code "15") (name "BUS6") (class "Default")
      (node (ref "E11") (pin "14") (pinfunction "Y3_14") (pintype "tri_state"))
      (node (ref "E11") (pin "7") (pinfunction "Y2_7") (pintype "tri_state"))
      (node (ref "E14") (pin "6") (pinfunction "D3_6") (pintype "input"))
      (node (ref "E15") (pin "6") (pinfunction "D3_6") (pintype "input"))
      (node (ref "J1") (pin "8") (pinfunction "8_8") (pintype "passive"))
      (node (ref "R11") (pin "1") (pinfunction "1_1") (pintype "passive"))
      (node (ref "R23") (pin "2") (pinfunction "2_2") (pintype "passive"))
    )
    (net (code "16") (name "BUS7") (class "Default")
      (node (ref "E10") (pin "14") (pinfunction "Y3_14") (pintype "tri_state"))
      (node (ref "E10") (pin "7") (pinfunction "Y2_7") (pintype "tri_state"))
      (node (ref "E12") (pin "3") (pinfunction "D1_3") (pintype "input"))
      (node (ref "E13") (pin "3") (pinfunction "D1_3") (pintype "input"))
      (node (ref "J1") (pin "6") (pinfunction "6_6") (pintype "passive"))
      (node (ref "R19") (pin "2") (pinfunction "2_2") (pintype "passive"))
      (node (ref "R7") (pin "1") (pinfunction "1_1") (pintype "passive"))
    )
    (net (code "17") (name "BUS8") (class "Default")
      (node (ref "E12") (pin "13") (pinfunction "D5_13") (pintype "input"))
      (node (ref "E13") (pin "13") (pinfunction "D5_13") (pintype "input"))
      (node (ref "E9") (pin "14") (pinfunction "Y3_14") (pintype "tri_state"))
      (node (ref "E9") (pin "7") (pinfunction "Y2_7") (pintype "tri_state"))
      (node (ref "J1") (pin "12") (pinfunction "12_12") (pintype "passive"))
      (node (ref "R1") (pin "2") (pinfunction "2_2") (pintype "passive"))
      (node (ref "R13") (pin "1") (pinfunction "1_1") (pintype "passive"))
    )
    (net (code "18") (name "BUS9") (class "Default")
      (node (ref "E11") (pin "12") (pinfunction "Y4_12") (pintype "tri_state"))
      (node (ref "E11") (pin "9") (pinfunction "Y1_9") (pintype "tri_state"))
      (node (ref "E14") (pin "11") (pinfunction "D4_11") (pintype "input"))
      (node (ref "E15") (pin "11") (pinfunction "D4_11") (pintype "input"))
      (node (ref "J1") (pin "10") (pinfunction "10_10") (pintype "passive"))
      (node (ref "R12") (pin "1") (pinfunction "1_1") (pintype "passive"))
      (node (ref "R24") (pin "2") (pinfunction "2_2") (pintype "passive"))
    )
    (net (code "19") (name "BUS10") (class "Default")
      (node (ref "E10") (pin "12") (pinfunction "Y4_12") (pintype "tri_state"))
      (node (ref "E10") (pin "9") (pinfunction "Y1_9") (pintype "tri_state"))
      (node (ref "E12") (pin "4") (pinfunction "D2_4") (pintype "input"))
      (node (ref "E13") (pin "4") (pinfunction "D2_4") (pintype "input"))
      (node (ref "J1") (pin "16") (pinfunction "16_16") (pintype "passive"))
      (node (ref "R20") (pin "2") (pinfunction "2_2") (pintype "passive"))
      (node (ref "R8") (pin "1") (pinfunction "1_1") (pintype "passive"))
    )
    (net (code "20") (name "BUS11") (class "Default")
      (node (ref "E12") (pin "14") (pinfunction "D6_14") (pintype "input"))
      (node (ref "E13") (pin "14") (pinfunction "D6_14") (pintype "input"))
      (node (ref "E9") (pin "12") (pinfunction "Y4_12") (pintype "tri_state"))
      (node (ref "E9") (pin "9") (pinfunction "Y1_9") (pintype "tri_state"))
      (node (ref "J1") (pin "14") (pinfunction "14_14") (pintype "passive"))
      (node (ref "R14") (pin "1") (pinfunction "1_1") (pintype "passive"))
      (node (ref "R2") (pin "2") (pinfunction "2_2") (pintype "passive"))
    )
    (net (code "21") (name "DISP0") (class "Default")
      (node (ref "E34") (pin "14") (pinfunction "2A2_14") (pintype "input"))
      (node (ref "E35") (pin "3") (pinfunction "C_3") (pintype "input"))
      (node (ref "E36") (pin "15") (pinfunction "Q6_15") (pintype "output"))
      (node (ref "J4") (pin "5") (pinfunction "5_5") (pintype "passive"))
    )
    (net (code "22") (name "DISP1") (class "Default")
      (node (ref "E34") (pin "4") (pinfunction "1A2_4") (pintype "input"))
      (node (ref "E35") (pin "2") (pinfunction "B_2") (pintype "input"))
      (node (ref "E36") (pin "5") (pinfunction "Q2_5") (pintype "output"))
      (node (ref "J4") (pin "6") (pinfunction "6_6") (pintype "passive"))
    )
    (net (code "23") (name "DISP2") (class "Default")
      (node (ref "E34") (pin "2") (pinfunction "1A1_2") (pintype "input"))
      (node (ref "E35") (pin "1") (pinfunction "A_1") (pintype "input"))
      (node (ref "E36") (pin "2") (pinfunction "Q1_2") (pintype "output"))
      (node (ref "J4") (pin "7") (pinfunction "7_7") (pintype "passive"))
    )
    (net (code "24") (name "DISPINH") (class "Default")
      (node (ref "E16") (pin "9") (pinfunction "Q_9") (pintype "output"))
      (node (ref "E22") (pin "12") (pinfunction "I1_12") (pintype "input"))
      (node (ref "J4") (pin "4") (pinfunction "4_4") (pintype "passive"))
    )
    (net (code "25") (name "DISPLAY0") (class "Default")
      (node (ref "E19") (pin "7") (pinfunction "1Y_7") (pintype "output"))
      (node (ref "J3") (pin "7") (pinfunction "7_7") (pintype "passive"))
    )
    (net (code "26") (name "DISPLAY1") (class "Default")
      (node (ref "E19") (pin "9") (pinfunction "2Y_9") (pintype "output"))
      (node (ref "J3") (pin "11") (pinfunction "11_11") (pintype "passive"))
    )
    (net (code "27") (name "DISPLAY2") (class "Default")
      (node (ref "E18") (pin "7") (pinfunction "1Y_7") (pintype "output"))
      (node (ref "J3") (pin "6") (pinfunction "6_6") (pintype "passive"))
    )
    (net (code "28") (name "E30PIN8") (class "Default")
      (node (ref "E21") (pin "11") (pinfunction "I2_11") (pintype "input"))
      (node (ref "E21") (pin "5") (pinfunction "I2_5") (pintype "input"))
      (node (ref "E30") (pin "8") (pinfunction "O_8") (pintype "output"))
    )
    (net (code "29") (name "ENT0") (class "Default")
      (node (ref "E11") (pin "8") (pinfunction "A4_8") (pintype "input"))
      (node (ref "E3") (pin "13") (pinfunction "QA_13") (pintype "output"))
      (node (ref "E36") (pin "14") (pinfunction "D6_14") (pintype "input"))
      (node (ref "E7") (pin "13") (pinfunction "D4_13") (pintype "input"))
    )
    (net (code "30") (name "ENT1") (class "Default")
      (node (ref "E10") (pin "8") (pinfunction "A4_8") (pintype "input"))
      (node (ref "E2") (pin "13") (pinfunction "QA_13") (pintype "output"))
      (node (ref "E36") (pin "4") (pinfunction "D2_4") (pintype "input"))
      (node (ref "E6") (pin "13") (pinfunction "D4_13") (pintype "input"))
    )
    (net (code "31") (name "ENT2") (class "Default")
      (node (ref "E1") (pin "13") (pinfunction "QA_13") (pintype "output"))
      (node (ref "E36") (pin "3") (pinfunction "D1_3") (pintype "input"))
      (node (ref "E5") (pin "13") (pinfunction "D4_13") (pintype "input"))
      (node (ref "E9") (pin "8") (pinfunction "A4_8") (pintype "input"))
    )
    (net (code "32") (name "GND") (class "Default")
      (node (ref "C1") (pin "2") (pinfunction "2_2") (pintype "passive"))
      (node (ref "C10") (pin "2") (pinfunction "2_2") (pintype "passive"))
      (node (ref "C11") (pin "2") (pinfunction "2_2") (pintype "passive"))
      (node (ref "C12") (pin "2") (pinfunction "2_2") (pintype "passive"))
      (node (ref "C13") (pin "2") (pinfunction "2_2") (pintype "passive"))
      (node (ref "C14") (pin "2") (pinfunction "2_2") (pintype "passive"))
      (node (ref "C15") (pin "2") (pinfunction "2_2") (pintype "passive"))
      (node (ref "C16") (pin "2") (pinfunction "2_2") (pintype "passive"))
      (node (ref "C17") (pin "2") (pinfunction "2_2") (pintype "passive"))
      (node (ref "C18") (pin "2") (pinfunction "2_2") (pintype "passive"))
      (node (ref "C19") (pin "2") (pinfunction "2_2") (pintype "passive"))
      (node (ref "C2") (pin "2") (pinfunction "2_2") (pintype "passive"))
      (node (ref "C20") (pin "2") (pinfunction "2_2") (pintype "passive"))
      (node (ref "C21") (pin "2") (pinfunction "2_2") (pintype "passive"))
      (node (ref "C22") (pin "2") (pinfunction "2_2") (pintype "passive"))
      (node (ref "C23") (pin "2") (pinfunction "2_2") (pintype "passive"))
      (node (ref "C24") (pin "2") (pinfunction "2_2") (pintype "passive"))
      (node (ref "C25") (pin "2") (pinfunction "2_2") (pintype "passive"))
      (node (ref "C26") (pin "2") (pinfunction "2_2") (pintype "passive"))
      (node (ref "C27") (pin "2") (pinfunction "2_2") (pintype "passive"))
      (node (ref "C28") (pin "2") (pinfunction "2_2") (pintype "passive"))
      (node (ref "C29") (pin "2") (pinfunction "2_2") (pintype "passive"))
      (node (ref "C3") (pin "2") (pinfunction "2_2") (pintype "passive"))
      (node (ref "C30") (pin "2") (pinfunction "2_2") (pintype "passive"))
      (node (ref "C31") (pin "2") (pinfunction "2_2") (pintype "passive"))
      (node (ref "C32") (pin "2") (pinfunction "2_2") (pintype "passive"))
      (node (ref "C33") (pin "2") (pinfunction "2_2") (pintype "passive"))
      (node (ref "C34") (pin "2") (pinfunction "2_2") (pintype "passive"))
      (node (ref "C35") (pin "2") (pinfunction "2_2") (pintype "passive"))
      (node (ref "C36") (pin "2") (pinfunction "2_2") (pintype "passive"))
      (node (ref "C38") (pin "-") (pinfunction "-_-") (pintype "passive"))
      (node (ref "C39") (pin "-") (pinfunction "-_-") (pintype "passive"))
      (node (ref "C4") (pin "2") (pinfunction "2_2") (pintype "passive"))
      (node (ref "C5") (pin "2") (pinfunction "2_2") (pintype "passive"))
      (node (ref "C6") (pin "2") (pinfunction "2_2") (pintype "passive"))
      (node (ref "C7") (pin "2") (pinfunction "2_2") (pintype "passive"))
      (node (ref "C8") (pin "2") (pinfunction "2_2") (pintype "passive"))
      (node (ref "C9") (pin "2") (pinfunction "2_2") (pintype "passive"))
      (node (ref "E1") (pin "3") (pinfunction "B_3") (pintype "input"))
      (node (ref "E1") (pin "4") (pinfunction "C_4") (pintype "input"))
      (node (ref "E1") (pin "5") (pinfunction "D_5") (pintype "input"))
      (node (ref "E17") (pin "1") (pinfunction "1G_1") (pintype "input"))
      (node (ref "E17") (pin "15") (pinfunction "2G_15") (pintype "input"))
      (node (ref "E18") (pin "1") (pinfunction "1G_1") (pintype "input"))
      (node (ref "E18") (pin "15") (pinfunction "2G_15") (pintype "input"))
      (node (ref "E19") (pin "1") (pinfunction "1G_1") (pintype "input"))
      (node (ref "E19") (pin "15") (pinfunction "2G_15") (pintype "input"))
      (node (ref "E2") (pin "3") (pinfunction "B_3") (pintype "input"))
      (node (ref "E2") (pin "4") (pinfunction "C_4") (pintype "input"))
      (node (ref "E2") (pin "5") (pinfunction "D_5") (pintype "input"))
      (node (ref "E25") (pin "3") (pinfunction "I0_3") (pintype "input"))
      (node (ref "E25") (pin "4") (pinfunction "I1_4") (pintype "input"))
      (node (ref "E3") (pin "3") (pinfunction "B_3") (pintype "input"))
      (node (ref "E3") (pin "4") (pinfunction "C_4") (pintype "input"))
      (node (ref "E3") (pin "5") (pinfunction "D_5") (pintype "input"))
      (node (ref "GND") (pin "1") (pinfunction "P_1") (pintype "passive"))
      (node (ref "J1") (pin "11") (pinfunction "11_11") (pintype "passive"))
      (node (ref "J1") (pin "13") (pinfunction "13_13") (pintype "passive"))
      (node (ref "J1") (pin "15") (pinfunction "15_15") (pintype "passive"))
      (node (ref "J1") (pin "17") (pinfunction "17_17") (pintype "passive"))
      (node (ref "J1") (pin "19") (pinfunction "19_19") (pintype "passive"))
      (node (ref "J1") (pin "21") (pinfunction "21_21") (pintype "passive"))
      (node (ref "J1") (pin "23") (pinfunction "23_23") (pintype "passive"))
      (node (ref "J1") (pin "25") (pinfunction "25_25") (pintype "passive"))
      (node (ref "J1") (pin "27") (pinfunction "27_27") (pintype "passive"))
      (node (ref "J1") (pin "29") (pinfunction "29_29") (pintype "passive"))
      (node (ref "J1") (pin "31") (pinfunction "31_31") (pintype "passive"))
      (node (ref "J1") (pin "33") (pinfunction "33_33") (pintype "passive"))
      (node (ref "J1") (pin "35") (pinfunction "35_35") (pintype "passive"))
      (node (ref "J1") (pin "37") (pinfunction "37_37") (pintype "passive"))
      (node (ref "J1") (pin "39") (pinfunction "39_39") (pintype "passive"))
      (node (ref "J2") (pin "11") (pinfunction "11_11") (pintype "passive"))
      (node (ref "J2") (pin "13") (pinfunction "13_13") (pintype "passive"))
      (node (ref "J2") (pin "15") (pinfunction "15_15") (pintype "passive"))
      (node (ref "J2") (pin "16") (pinfunction "16_16") (pintype "passive"))
      (node (ref "J2") (pin "17") (pinfunction "17_17") (pintype "passive"))
      (node (ref "J2") (pin "19") (pinfunction "19_19") (pintype "passive"))
      (node (ref "J2") (pin "21") (pinfunction "21_21") (pintype "passive"))
      (node (ref "J2") (pin "23") (pinfunction "23_23") (pintype "passive"))
      (node (ref "J2") (pin "25") (pinfunction "25_25") (pintype "passive"))
      (node (ref "J2") (pin "27") (pinfunction "27_27") (pintype "passive"))
      (node (ref "J2") (pin "29") (pinfunction "29_29") (pintype "passive"))
      (node (ref "J2") (pin "31") (pinfunction "31_31") (pintype "passive"))
      (node (ref "J2") (pin "33") (pinfunction "33_33") (pintype "passive"))
      (node (ref "J2") (pin "35") (pinfunction "35_35") (pintype "passive"))
      (node (ref "J2") (pin "37") (pinfunction "37_37") (pintype "passive"))
      (node (ref "J2") (pin "39") (pinfunction "39_39") (pintype "passive"))
      (node (ref "J3") (pin "8") (pinfunction "8_8") (pintype "passive"))
      (node (ref "J4") (pin "8") (pinfunction "8_8") (pintype "passive"))
      (node (ref "R1") (pin "1") (pinfunction "1_1") (pintype "passive"))
      (node (ref "R17") (pin "1") (pinfunction "1_1") (pintype "passive"))
      (node (ref "R18") (pin "1") (pinfunction "1_1") (pintype "passive"))
      (node (ref "R19") (pin "1") (pinfunction "1_1") (pintype "passive"))
      (node (ref "R2") (pin "1") (pinfunction "1_1") (pintype "passive"))
      (node (ref "R20") (pin "1") (pinfunction "1_1") (pintype "passive"))
      (node (ref "R21") (pin "1") (pinfunction "1_1") (pintype "passive"))
      (node (ref "R22") (pin "1") (pinfunction "1_1") (pintype "passive"))
      (node (ref "R23") (pin "1") (pinfunction "1_1") (pintype "passive"))
      (node (ref "R24") (pin "1") (pinfunction "1_1") (pintype "passive"))
      (node (ref "R27") (pin "1") (pinfunction "1_1") (pintype "passive"))
      (node (ref "R3") (pin "1") (pinfunction "1_1") (pintype "passive"))
      (node (ref "R30") (pin "1") (pinfunction "1_1") (pintype "passive"))
      (node (ref "R4") (pin "1") (pinfunction "1_1") (pintype "passive"))
    )
    (net (code "33") (name "KEYSTB") (class "Default")
      (node (ref "E24") (pin "1") (pinfunction "I_1") (pintype "input"))
      (node (ref "E8") (pin "5") (pinfunction "I1_5") (pintype "input"))
      (node (ref "J4") (pin "2") (pinfunction "2_2") (pintype "passive"))
    )
    (net (code "34") (name "LDSR") (class "Default")
      (node (ref "E33") (pin "13") (pinfunction "O_13") (pintype "output"))
      (node (ref "E5") (pin "9") (pinfunction "CLK_9") (pintype "input"))
      (node (ref "E6") (pin "9") (pinfunction "CLK_9") (pintype "input"))
      (node (ref "E7") (pin "9") (pinfunction "CLK_9") (pintype "input"))
    )
    (net (code "35") (name "MH0") (class "Default")
      (node (ref "E20") (pin "9") (pinfunction "Q_9") (pintype "output"))
      (node (ref "E22") (pin "11") (pinfunction "I0_11") (pintype "input"))
      (node (ref "E8") (pin "13") (pinfunction "I1_13") (pintype "input"))
    )
    (net (code "36") (name "MPXA") (class "Default")
      (node (ref "E17") (pin "14") (pinfunction "A_14") (pintype "input"))
      (node (ref "E18") (pin "14") (pinfunction "A_14") (pintype "input"))
      (node (ref "E19") (pin "14") (pinfunction "A_14") (pintype "input"))
      (node (ref "J4") (pin "14") (pinfunction "14_14") (pintype "passive"))
    )
    (net (code "37") (name "MPXB") (class "Default")
      (node (ref "E17") (pin "2") (pinfunction "B_2") (pintype "input"))
      (node (ref "E18") (pin "2") (pinfunction "B_2") (pintype "input"))
      (node (ref "E19") (pin "2") (pinfunction "B_2") (pintype "input"))
      (node (ref "J4") (pin "13") (pinfunction "13_13") (pintype "passive"))
    )
    (net (code "38") (name "NUM") (class "Default")
      (node (ref "E16") (pin "12") (pinfunction "D_12") (pintype "input"))
      (node (ref "E21") (pin "13") (pinfunction "I2_13") (pintype "input"))
      (node (ref "E8") (pin "4") (pinfunction "I0_4") (pintype "input"))
      (node (ref "J4") (pin "11") (pinfunction "11_11") (pintype "passive"))
    )
    (net (code "39") (name "NUMCLK") (class "Default")
      (node (ref "E1") (pin "8") (pinfunction "CK2_8") (pintype "input"))
      (node (ref "E1") (pin "9") (pinfunction "CK1_9") (pintype "input"))
      (node (ref "E2") (pin "8") (pinfunction "CK2_8") (pintype "input"))
      (node (ref "E2") (pin "9") (pinfunction "CK1_9") (pintype "input"))
      (node (ref "E3") (pin "8") (pinfunction "CK2_8") (pintype "input"))
      (node (ref "E3") (pin "9") (pinfunction "CK1_9") (pintype "input"))
      (node (ref "E8") (pin "6") (pinfunction "O_6") (pintype "output"))
    )
    (net (code "40") (name "Net-(E1A-QB)") (class "Default")
      (node (ref "E1") (pin "12") (pinfunction "QB_12") (pintype "output"))
      (node (ref "E5") (pin "12") (pinfunction "D3_12") (pintype "input"))
      (node (ref "E9") (pin "6") (pinfunction "A3_6") (pintype "input"))
    )
    (net (code "41") (name "Net-(E1A-QC)") (class "Default")
      (node (ref "E1") (pin "11") (pinfunction "QC_11") (pintype "output"))
      (node (ref "E5") (pin "5") (pinfunction "D2_5") (pintype "input"))
      (node (ref "E9") (pin "4") (pinfunction "A2_4") (pintype "input"))
    )
    (net (code "42") (name "Net-(E1A-QD)") (class "Default")
      (node (ref "E1") (pin "10") (pinfunction "QD_10") (pintype "output"))
      (node (ref "E5") (pin "4") (pinfunction "D1_4") (pintype "input"))
      (node (ref "E9") (pin "2") (pinfunction "A1_2") (pintype "input"))
    )
    (net (code "43") (name "Net-(E4B-C)") (class "Default")
      (node (ref "C37") (pin "2") (pinfunction "2_2") (pintype "passive"))
      (node (ref "C40") (pin "2") (pinfunction "2_2") (pintype "passive"))
      (node (ref "E4") (pin "6") (pinfunction "C_6") (pintype "input"))
    )
    (net (code "44") (name "Net-(E4B-Q)") (class "Default")
      (node (ref "E4") (pin "5") (pinfunction "Q_5") (pintype "output"))
      (node (ref "E8") (pin "10") (pinfunction "I1_10") (pintype "input"))
      (node (ref "E8") (pin "12") (pinfunction "I0_12") (pintype "input"))
    )
    (net (code "45") (name "Net-(E4B-R{slash}C)") (class "Default")
      (node (ref "C37") (pin "1") (pinfunction "1_1") (pintype "passive"))
      (node (ref "C40") (pin "1") (pinfunction "1_1") (pintype "passive"))
      (node (ref "E4") (pin "7") (pinfunction "R/C_7") (pintype "input"))
      (node (ref "R25") (pin "2") (pinfunction "2_2") (pintype "passive"))
    )
    (net (code "46") (name "Net-(E5A-Q1)") (class "Default")
      (node (ref "E5") (pin "2") (pinfunction "Q1_2") (pintype "output"))
      (node (ref "E9") (pin "17") (pinfunction "A4_17") (pintype "input"))
    )
    (net (code "47") (name "Net-(E5A-Q2)") (class "Default")
      (node (ref "E5") (pin "7") (pinfunction "Q2_7") (pintype "output"))
      (node (ref "E9") (pin "15") (pinfunction "A3_15") (pintype "input"))
    )
    (net (code "48") (name "Net-(E5A-Q3)") (class "Default")
      (node (ref "E5") (pin "10") (pinfunction "Q3_10") (pintype "output"))
      (node (ref "E9") (pin "13") (pinfunction "A2_13") (pintype "input"))
    )
    (net (code "49") (name "Net-(E5A-Q4)") (class "Default")
      (node (ref "E5") (pin "15") (pinfunction "Q4_15") (pintype "output"))
      (node (ref "E9") (pin "11") (pinfunction "A1_11") (pintype "input"))
    )
    (net (code "50") (name "Net-(E10A-A1)") (class "Default")
      (node (ref "E10") (pin "2") (pinfunction "A1_2") (pintype "input"))
      (node (ref "E2") (pin "10") (pinfunction "QD_10") (pintype "output"))
      (node (ref "E6") (pin "4") (pinfunction "D1_4") (pintype "input"))
    )
    (net (code "51") (name "Net-(E10A-A2)") (class "Default")
      (node (ref "E10") (pin "4") (pinfunction "A2_4") (pintype "input"))
      (node (ref "E2") (pin "11") (pinfunction "QC_11") (pintype "output"))
      (node (ref "E6") (pin "5") (pinfunction "D2_5") (pintype "input"))
    )
    (net (code "52") (name "Net-(E10A-A3)") (class "Default")
      (node (ref "E10") (pin "6") (pinfunction "A3_6") (pintype "input"))
      (node (ref "E2") (pin "12") (pinfunction "QB_12") (pintype "output"))
      (node (ref "E6") (pin "12") (pinfunction "D3_12") (pintype "input"))
    )
    (net (code "53") (name "Net-(E10B-A1)") (class "Default")
      (node (ref "E10") (pin "11") (pinfunction "A1_11") (pintype "input"))
      (node (ref "E6") (pin "15") (pinfunction "Q4_15") (pintype "output"))
    )
    (net (code "54") (name "Net-(E10B-A2)") (class "Default")
      (node (ref "E10") (pin "13") (pinfunction "A2_13") (pintype "input"))
      (node (ref "E6") (pin "10") (pinfunction "Q3_10") (pintype "output"))
    )
    (net (code "55") (name "Net-(E10B-A3)") (class "Default")
      (node (ref "E10") (pin "15") (pinfunction "A3_15") (pintype "input"))
      (node (ref "E6") (pin "7") (pinfunction "Q2_7") (pintype "output"))
    )
    (net (code "56") (name "Net-(E10B-A4)") (class "Default")
      (node (ref "E10") (pin "17") (pinfunction "A4_17") (pintype "input"))
      (node (ref "E6") (pin "2") (pinfunction "Q1_2") (pintype "output"))
    )
    (net (code "57") (name "Net-(E11A-A1)") (class "Default")
      (node (ref "E11") (pin "2") (pinfunction "A1_2") (pintype "input"))
      (node (ref "E3") (pin "10") (pinfunction "QD_10") (pintype "output"))
      (node (ref "E7") (pin "4") (pinfunction "D1_4") (pintype "input"))
    )
    (net (code "58") (name "Net-(E11A-A2)") (class "Default")
      (node (ref "E11") (pin "4") (pinfunction "A2_4") (pintype "input"))
      (node (ref "E3") (pin "11") (pinfunction "QC_11") (pintype "output"))
      (node (ref "E7") (pin "5") (pinfunction "D2_5") (pintype "input"))
    )
    (net (code "59") (name "Net-(E11A-A3)") (class "Default")
      (node (ref "E11") (pin "6") (pinfunction "A3_6") (pintype "input"))
      (node (ref "E3") (pin "12") (pinfunction "QB_12") (pintype "output"))
      (node (ref "E7") (pin "12") (pinfunction "D3_12") (pintype "input"))
    )
    (net (code "60") (name "Net-(E11B-A1)") (class "Default")
      (node (ref "E11") (pin "11") (pinfunction "A1_11") (pintype "input"))
      (node (ref "E7") (pin "15") (pinfunction "Q4_15") (pintype "output"))
    )
    (net (code "61") (name "Net-(E11B-A2)") (class "Default")
      (node (ref "E11") (pin "13") (pinfunction "A2_13") (pintype "input"))
      (node (ref "E7") (pin "10") (pinfunction "Q3_10") (pintype "output"))
    )
    (net (code "62") (name "Net-(E11B-A3)") (class "Default")
      (node (ref "E11") (pin "15") (pinfunction "A3_15") (pintype "input"))
      (node (ref "E7") (pin "7") (pinfunction "Q2_7") (pintype "output"))
    )
    (net (code "63") (name "Net-(E11B-A4)") (class "Default")
      (node (ref "E11") (pin "17") (pinfunction "A4_17") (pintype "input"))
      (node (ref "E7") (pin "2") (pinfunction "Q1_2") (pintype "output"))
    )
    (net (code "64") (name "Net-(E12A-Q1)") (class "Default")
      (node (ref "E12") (pin "2") (pinfunction "Q1_2") (pintype "output"))
      (node (ref "E17") (pin "4") (pinfunction "1C2_4") (pintype "input"))
    )
    (net (code "65") (name "Net-(E12A-Q2)") (class "Default")
      (node (ref "E12") (pin "5") (pinfunction "Q2_5") (pintype "output"))
      (node (ref "E17") (pin "6") (pinfunction "1C0_6") (pintype "input"))
    )
    (net (code "66") (name "Net-(E12A-Q3)") (class "Default")
      (node (ref "E12") (pin "7") (pinfunction "Q3_7") (pintype "output"))
      (node (ref "E17") (pin "13") (pinfunction "2C3_13") (pintype "input"))
    )
    (net (code "67") (name "Net-(E12A-Q4)") (class "Default")
      (node (ref "E12") (pin "10") (pinfunction "Q4_10") (pintype "output"))
      (node (ref "E17") (pin "11") (pinfunction "2C1_11") (pintype "input"))
    )
    (net (code "68") (name "Net-(E12A-Q5)") (class "Default")
      (node (ref "E12") (pin "12") (pinfunction "Q5_12") (pintype "output"))
      (node (ref "E17") (pin "12") (pinfunction "2C2_12") (pintype "input"))
    )
    (net (code "69") (name "Net-(E12A-Q6)") (class "Default")
      (node (ref "E12") (pin "15") (pinfunction "Q6_15") (pintype "output"))
      (node (ref "E17") (pin "10") (pinfunction "2C0_10") (pintype "input"))
    )
    (net (code "70") (name "Net-(E13A-Q1)") (class "Default")
      (node (ref "E13") (pin "2") (pinfunction "Q1_2") (pintype "output"))
      (node (ref "E19") (pin "12") (pinfunction "2C2_12") (pintype "input"))
    )
    (net (code "71") (name "Net-(E13A-Q2)") (class "Default")
      (node (ref "E13") (pin "5") (pinfunction "Q2_5") (pintype "output"))
      (node (ref "E19") (pin "10") (pinfunction "2C0_10") (pintype "input"))
    )
    (net (code "72") (name "Net-(E13A-Q3)") (class "Default")
      (node (ref "E13") (pin "7") (pinfunction "Q3_7") (pintype "output"))
      (node (ref "E18") (pin "3") (pinfunction "1C3_3") (pintype "input"))
    )
    (net (code "73") (name "Net-(E13A-Q4)") (class "Default")
      (node (ref "E13") (pin "10") (pinfunction "Q4_10") (pintype "output"))
      (node (ref "E18") (pin "5") (pinfunction "1C1_5") (pintype "input"))
    )
    (net (code "74") (name "Net-(E13A-Q5)") (class "Default")
      (node (ref "E13") (pin "12") (pinfunction "Q5_12") (pintype "output"))
      (node (ref "E18") (pin "4") (pinfunction "1C2_4") (pintype "input"))
    )
    (net (code "75") (name "Net-(E13A-Q6)") (class "Default")
      (node (ref "E13") (pin "15") (pinfunction "Q6_15") (pintype "output"))
      (node (ref "E18") (pin "6") (pinfunction "1C0_6") (pintype "input"))
    )
    (net (code "76") (name "Net-(E14A-Q1)") (class "Default")
      (node (ref "E14") (pin "2") (pinfunction "Q1_2") (pintype "output"))
      (node (ref "E18") (pin "13") (pinfunction "2C3_13") (pintype "input"))
    )
    (net (code "77") (name "Net-(E14A-Q2)") (class "Default")
      (node (ref "E14") (pin "5") (pinfunction "Q2_5") (pintype "output"))
      (node (ref "E18") (pin "11") (pinfunction "2C1_11") (pintype "input"))
    )
    (net (code "78") (name "Net-(E14A-Q3)") (class "Default")
      (node (ref "E14") (pin "7") (pinfunction "Q3_7") (pintype "output"))
      (node (ref "E18") (pin "12") (pinfunction "2C2_12") (pintype "input"))
    )
    (net (code "79") (name "Net-(E14A-Q4)") (class "Default")
      (node (ref "E14") (pin "10") (pinfunction "Q4_10") (pintype "output"))
      (node (ref "E18") (pin "10") (pinfunction "2C0_10") (pintype "input"))
    )
    (net (code "80") (name "Net-(E14A-Q5)") (class "Default")
      (node (ref "E14") (pin "12") (pinfunction "Q5_12") (pintype "output"))
      (node (ref "E17") (pin "3") (pinfunction "1C3_3") (pintype "input"))
    )
    (net (code "81") (name "Net-(E14A-Q6)") (class "Default")
      (node (ref "E14") (pin "15") (pinfunction "Q6_15") (pintype "output"))
      (node (ref "E17") (pin "5") (pinfunction "1C1_5") (pintype "input"))
    )
    (net (code "82") (name "Net-(E15A-Q1)") (class "Default")
      (node (ref "E15") (pin "2") (pinfunction "Q1_2") (pintype "output"))
      (node (ref "E19") (pin "3") (pinfunction "1C3_3") (pintype "input"))
    )
    (net (code "83") (name "Net-(E15A-Q2)") (class "Default")
      (node (ref "E15") (pin "5") (pinfunction "Q2_5") (pintype "output"))
      (node (ref "E19") (pin "5") (pinfunction "1C1_5") (pintype "input"))
    )
    (net (code "84") (name "Net-(E15A-Q3)") (class "Default")
      (node (ref "E15") (pin "7") (pinfunction "Q3_7") (pintype "output"))
      (node (ref "E19") (pin "4") (pinfunction "1C2_4") (pintype "input"))
    )
    (net (code "85") (name "Net-(E15A-Q4)") (class "Default")
      (node (ref "E15") (pin "10") (pinfunction "Q4_10") (pintype "output"))
      (node (ref "E19") (pin "6") (pinfunction "1C0_6") (pintype "input"))
    )
    (net (code "86") (name "Net-(E15A-Q5)") (class "Default")
      (node (ref "E15") (pin "12") (pinfunction "Q5_12") (pintype "output"))
      (node (ref "E19") (pin "13") (pinfunction "2C3_13") (pintype "input"))
    )
    (net (code "87") (name "Net-(E15A-Q6)") (class "Default")
      (node (ref "E15") (pin "15") (pinfunction "Q6_15") (pintype "output"))
      (node (ref "E19") (pin "11") (pinfunction "2C1_11") (pintype "input"))
    )
    (net (code "88") (name "Net-(E16A-CLK)") (class "Default")
      (node (ref "E16") (pin "3") (pinfunction "CLK_3") (pintype "input"))
      (node (ref "E21") (pin "12") (pinfunction "O_12") (pintype "output"))
    )
    (net (code "89") (name "Net-(E20A-PRE)") (class "Default")
      (node (ref "E20") (pin "4") (pinfunction "PRE_4") (pintype "input"))
      (node (ref "E26") (pin "8") (pinfunction "~{Q4}_8") (pintype "output"))
    )
    (net (code "90") (name "Net-(E20B-CLK)") (class "Default")
      (node (ref "E20") (pin "11") (pinfunction "CLK_11") (pintype "input"))
      (node (ref "E22") (pin "1") (pinfunction "O_1") (pintype "output"))
      (node (ref "E4") (pin "9") (pinfunction "A_9") (pintype "input"))
    )
    (net (code "91") (name "Net-(E21A-I0)") (class "Default")
      (node (ref "E21") (pin "1") (pinfunction "I0_1") (pintype "input"))
      (node (ref "E24") (pin "4") (pinfunction "O_4") (pintype "output"))
    )
    (net (code "92") (name "Net-(E21B-I0)") (class "Default")
      (node (ref "E21") (pin "3") (pinfunction "I0_3") (pintype "input"))
      (node (ref "E21") (pin "4") (pinfunction "I1_4") (pintype "input"))
      (node (ref "E22") (pin "4") (pinfunction "O_4") (pintype "output"))
    )
    (net (code "93") (name "Net-(E21C-O)") (class "Default")
      (node (ref "E21") (pin "8") (pinfunction "O_8") (pintype "output"))
      (node (ref "E23") (pin "9") (pinfunction "I_9") (pintype "input"))
    )
    (net (code "94") (name "Net-(E22A-I0)") (class "Default")
      (node (ref "E22") (pin "2") (pinfunction "I0_2") (pintype "input"))
      (node (ref "E32") (pin "6") (pinfunction "O_6") (pintype "output"))
    )
    (net (code "95") (name "Net-(E22A-I1)") (class "Default")
      (node (ref "E22") (pin "3") (pinfunction "I1_3") (pintype "input"))
      (node (ref "E33") (pin "1") (pinfunction "O_1") (pintype "output"))
    )
    (net (code "96") (name "Net-(E22B-I0)") (class "Default")
      (node (ref "E22") (pin "5") (pinfunction "I0_5") (pintype "input"))
      (node (ref "E8") (pin "3") (pinfunction "O_3") (pintype "output"))
    )
    (net (code "97") (name "Net-(E22C-I0)") (class "Default")
      (node (ref "E22") (pin "8") (pinfunction "I0_8") (pintype "input"))
      (node (ref "E25") (pin "12") (pinfunction "O_12") (pintype "output"))
    )
    (net (code "98") (name "Net-(E22C-I1)") (class "Default")
      (node (ref "E22") (pin "9") (pinfunction "I1_9") (pintype "input"))
      (node (ref "E25") (pin "8") (pinfunction "O_8") (pintype "output"))
    )
    (net (code "99") (name "Net-(E22C-O)") (class "Default")
      (node (ref "E22") (pin "10") (pinfunction "O_10") (pintype "output"))
      (node (ref "E29") (pin "4") (pinfunction "G2A_4") (pintype "input"))
      (node (ref "E29") (pin "5") (pinfunction "G2B_5") (pintype "input"))
      (node (ref "E31") (pin "15") (pinfunction "2G_15") (pintype "input"))
    )
    (net (code "100") (name "Net-(E22D-O)") (class "Default")
      (node (ref "E22") (pin "13") (pinfunction "O_13") (pintype "output"))
      (node (ref "E30") (pin "4") (pinfunction "I0_4") (pintype "input"))
    )
    (net (code "101") (name "Net-(E23A-I)") (class "Default")
      (node (ref "E23") (pin "1") (pinfunction "I_1") (pintype "input"))
      (node (ref "E33") (pin "4") (pinfunction "O_4") (pintype "output"))
    )
    (net (code "102") (name "Net-(E23E-I)") (class "Default")
      (node (ref "E23") (pin "11") (pinfunction "I_11") (pintype "input"))
      (node (ref "E24") (pin "10") (pinfunction "O_10") (pintype "output"))
    )
    (net (code "103") (name "Net-(E23F-I)") (class "Default")
      (node (ref "E23") (pin "13") (pinfunction "I_13") (pintype "input"))
      (node (ref "E25") (pin "6") (pinfunction "O_6") (pintype "output"))
    )
    (net (code "104") (name "Net-(E24D-O)") (class "Default")
      (node (ref "E24") (pin "8") (pinfunction "O_8") (pintype "output"))
      (node (ref "E32") (pin "5") (pinfunction "I1_5") (pintype "input"))
    )
    (net (code "105") (name "Net-(E24F-O)") (class "Default")
      (node (ref "E24") (pin "12") (pinfunction "O_12") (pintype "output"))
      (node (ref "E25") (pin "10") (pinfunction "I1_10") (pintype "input"))
      (node (ref "E28") (pin "1") (pinfunction "1G_1") (pintype "input"))
      (node (ref "E28") (pin "15") (pinfunction "2G_15") (pintype "input"))
      (node (ref "E33") (pin "6") (pinfunction "I1_6") (pintype "input"))
    )
    (net (code "106") (name "Net-(E25A-I0)") (class "Default")
      (node (ref "E25") (pin "1") (pinfunction "I0_1") (pintype "input"))
      (node (ref "E26") (pin "16") (pinfunction "Q1_16") (pintype "output"))
      (node (ref "E29") (pin "3") (pinfunction "C_3") (pintype "input"))
    )
    (net (code "107") (name "Net-(E25A-I2)") (class "Default")
      (node (ref "E25") (pin "13") (pinfunction "I2_13") (pintype "input"))
      (node (ref "E26") (pin "15") (pinfunction "Q2_15") (pintype "output"))
      (node (ref "E27") (pin "3") (pinfunction "I_3") (pintype "input"))
      (node (ref "E29") (pin "2") (pinfunction "B_2") (pintype "input"))
      (node (ref "E30") (pin "1") (pinfunction "I0_1") (pintype "input"))
    )
    (net (code "108") (name "Net-(E25B-I2)") (class "Default")
      (node (ref "D1") (pin "A") (pinfunction "A_A") (pintype "passive"))
      (node (ref "D2") (pin "A") (pinfunction "A_A") (pintype "passive"))
      (node (ref "E25") (pin "5") (pinfunction "I2_5") (pintype "input"))
      (node (ref "R37") (pin "1") (pinfunction "1_1") (pintype "passive"))
    )
    (net (code "109") (name "Net-(E25C-I0)") (class "Default")
      (node (ref "E25") (pin "9") (pinfunction "I0_9") (pintype "input"))
      (node (ref "E26") (pin "9") (pinfunction "Q4_9") (pintype "output"))
    )
    (net (code "110") (name "Net-(E26A-Q3)") (class "Default")
      (node (ref "E26") (pin "10") (pinfunction "Q3_10") (pintype "output"))
      (node (ref "E29") (pin "1") (pinfunction "A_1") (pintype "input"))
    )
    (net (code "111") (name "Net-(E27A-O)") (class "Default")
      (node (ref "E27") (pin "2") (pinfunction "O_2") (pintype "output"))
      (node (ref "E30") (pin "12") (pinfunction "I0_12") (pintype "input"))
    )
    (net (code "112") (name "Net-(E27B-O)") (class "Default")
      (node (ref "E27") (pin "4") (pinfunction "O_4") (pintype "output"))
      (node (ref "E31") (pin "12") (pinfunction "2A1_12") (pintype "input"))
    )
    (net (code "113") (name "Net-(E27C-O)") (class "Default")
      (node (ref "E27") (pin "6") (pinfunction "O_6") (pintype "output"))
      (node (ref "E30") (pin "13") (pinfunction "I1_13") (pintype "input"))
    )
    (net (code "114") (name "Net-(E28A-1A1)") (class "Default")
      (node (ref "E28") (pin "2") (pinfunction "1A1_2") (pintype "input"))
      (node (ref "E29") (pin "9") (pinfunction "Y6_9") (pintype "output"))
      (node (ref "E32") (pin "2") (pinfunction "I1_2") (pintype "input"))
    )
    (net (code "115") (name "Net-(E28A-1A2)") (class "Default")
      (node (ref "E28") (pin "4") (pinfunction "1A2_4") (pintype "input"))
      (node (ref "E29") (pin "7") (pinfunction "Y7_7") (pintype "output"))
      (node (ref "E30") (pin "10") (pinfunction "I1_10") (pintype "input"))
      (node (ref "E32") (pin "1") (pinfunction "I0_1") (pintype "input"))
    )
    (net (code "116") (name "Net-(E28A-1A3)") (class "Default")
      (node (ref "E28") (pin "6") (pinfunction "1A3_6") (pintype "input"))
      (node (ref "E30") (pin "9") (pinfunction "I0_9") (pintype "input"))
      (node (ref "E31") (pin "6") (pinfunction "1A3_6") (pintype "input"))
      (node (ref "E32") (pin "8") (pinfunction "O_8") (pintype "output"))
      (node (ref "E33") (pin "5") (pinfunction "I0_5") (pintype "input"))
    )
    (net (code "117") (name "Net-(E28A-2A2)") (class "Default")
      (node (ref "E28") (pin "14") (pinfunction "2A2_14") (pintype "input"))
      (node (ref "E30") (pin "11") (pinfunction "O_11") (pintype "output"))
    )
    (net (code "118") (name "Net-(E29A-Y0)") (class "Default")
      (node (ref "E29") (pin "15") (pinfunction "Y0_15") (pintype "output"))
      (node (ref "E33") (pin "8") (pinfunction "I0_8") (pintype "input"))
    )
    (net (code "119") (name "Net-(E29A-Y1)") (class "Default")
      (node (ref "E29") (pin "14") (pinfunction "Y1_14") (pintype "output"))
      (node (ref "E33") (pin "12") (pinfunction "I1_12") (pintype "input"))
    )
    (net (code "120") (name "Net-(E29A-Y2)") (class "Default")
      (node (ref "E29") (pin "13") (pinfunction "Y2_13") (pintype "output"))
      (node (ref "E30") (pin "2") (pinfunction "I1_2") (pintype "input"))
      (node (ref "E32") (pin "10") (pinfunction "I1_10") (pintype "input"))
    )
    (net (code "121") (name "Net-(E29A-Y3)") (class "Default")
      (node (ref "E29") (pin "12") (pinfunction "Y3_12") (pintype "output"))
      (node (ref "E32") (pin "9") (pinfunction "I0_9") (pintype "input"))
    )
    (net (code "122") (name "Net-(E29A-Y4)") (class "Default")
      (node (ref "E29") (pin "11") (pinfunction "Y4_11") (pintype "output"))
      (node (ref "E31") (pin "10") (pinfunction "1A4_10") (pintype "input"))
    )
    (net (code "123") (name "Net-(E29A-Y5)") (class "Default")
      (node (ref "E29") (pin "10") (pinfunction "Y5_10") (pintype "output"))
      (node (ref "E31") (pin "2") (pinfunction "1A1_2") (pintype "input"))
    )
    (net (code "124") (name "Net-(E30A-O)") (class "Default")
      (node (ref "E30") (pin "3") (pinfunction "O_3") (pintype "output"))
      (node (ref "E31") (pin "14") (pinfunction "2A2_14") (pintype "input"))
    )
    (net (code "125") (name "Net-(E30B-O)") (class "Default")
      (node (ref "E30") (pin "6") (pinfunction "O_6") (pintype "output"))
      (node (ref "E34") (pin "1") (pinfunction "1G_1") (pintype "input"))
      (node (ref "E34") (pin "15") (pinfunction "2G_15") (pintype "input"))
      (node (ref "E35") (pin "4") (pinfunction "G2A_4") (pintype "input"))
      (node (ref "E35") (pin "5") (pinfunction "G2B_5") (pintype "input"))
    )
    (net (code "126") (name "Net-(E31A-1A2)") (class "Default")
      (node (ref "E31") (pin "4") (pinfunction "1A2_4") (pintype "input"))
      (node (ref "E32") (pin "3") (pinfunction "O_3") (pintype "output"))
    )
    (net (code "127") (name "Net-(E31A-1Y1)") (class "Default")
      (node (ref "D2") (pin "C") (pinfunction "C_C") (pintype "passive"))
      (node (ref "E31") (pin "3") (pinfunction "1Y1_3") (pintype "tri_state"))
    )
    (net (code "128") (name "Net-(E31A-1Y2)") (class "Default")
      (node (ref "D1") (pin "C") (pinfunction "C_C") (pintype "passive"))
      (node (ref "E31") (pin "5") (pinfunction "1Y2_5") (pintype "tri_state"))
    )
    (net (code "129") (name "Net-(E32D-I0)") (class "Default")
      (node (ref "E32") (pin "12") (pinfunction "I0_12") (pintype "input"))
      (node (ref "E35") (pin "11") (pinfunction "Y4_11") (pintype "output"))
    )
    (net (code "130") (name "Net-(E33C-O)") (class "Default")
      (node (ref "E33") (pin "10") (pinfunction "O_10") (pintype "output"))
      (node (ref "E36") (pin "9") (pinfunction "CLK_9") (pintype "input"))
    )
    (net (code "131") (name "Net-(E34A-1A3)") (class "Default")
      (node (ref "E34") (pin "6") (pinfunction "1A3_6") (pintype "input"))
      (node (ref "E35") (pin "9") (pinfunction "Y6_9") (pintype "output"))
    )
    (net (code "132") (name "Net-(E34A-2A1)") (class "Default")
      (node (ref "E34") (pin "12") (pinfunction "2A1_12") (pintype "input"))
      (node (ref "E35") (pin "10") (pinfunction "Y5_10") (pintype "output"))
    )
    (net (code "133") (name "POWCK") (class "Default")
      (node (ref "E24") (pin "11") (pinfunction "I_11") (pintype "input"))
      (node (ref "J2") (pin "28") (pinfunction "28_28") (pintype "passive"))
      (node (ref "R33") (pin "1") (pinfunction "1_1") (pintype "passive"))
    )
    (net (code "134") (name "THIS") (class "Default")
      (node (ref "E20") (pin "5") (pinfunction "Q_5") (pintype "output"))
      (node (ref "E28") (pin "12") (pinfunction "2A1_12") (pintype "input"))
    )
    (net (code "135") (name "VCC") (class "Default")
      (node (ref "C1") (pin "1") (pinfunction "1_1") (pintype "passive"))
      (node (ref "C10") (pin "1") (pinfunction "1_1") (pintype "passive"))
      (node (ref "C11") (pin "1") (pinfunction "1_1") (pintype "passive"))
      (node (ref "C12") (pin "1") (pinfunction "1_1") (pintype "passive"))
      (node (ref "C13") (pin "1") (pinfunction "1_1") (pintype "passive"))
      (node (ref "C14") (pin "1") (pinfunction "1_1") (pintype "passive"))
      (node (ref "C15") (pin "1") (pinfunction "1_1") (pintype "passive"))
      (node (ref "C16") (pin "1") (pinfunction "1_1") (pintype "passive"))
      (node (ref "C17") (pin "1") (pinfunction "1_1") (pintype "passive"))
      (node (ref "C18") (pin "1") (pinfunction "1_1") (pintype "passive"))
      (node (ref "C19") (pin "1") (pinfunction "1_1") (pintype "passive"))
      (node (ref "C2") (pin "1") (pinfunction "1_1") (pintype "passive"))
      (node (ref "C20") (pin "1") (pinfunction "1_1") (pintype "passive"))
      (node (ref "C21") (pin "1") (pinfunction "1_1") (pintype "passive"))
      (node (ref "C22") (pin "1") (pinfunction "1_1") (pintype "passive"))
      (node (ref "C23") (pin "1") (pinfunction "1_1") (pintype "passive"))
      (node (ref "C24") (pin "1") (pinfunction "1_1") (pintype "passive"))
      (node (ref "C25") (pin "1") (pinfunction "1_1") (pintype "passive"))
      (node (ref "C26") (pin "1") (pinfunction "1_1") (pintype "passive"))
      (node (ref "C27") (pin "1") (pinfunction "1_1") (pintype "passive"))
      (node (ref "C28") (pin "1") (pinfunction "1_1") (pintype "passive"))
      (node (ref "C29") (pin "1") (pinfunction "1_1") (pintype "passive"))
      (node (ref "C3") (pin "1") (pinfunction "1_1") (pintype "passive"))
      (node (ref "C30") (pin "1") (pinfunction "1_1") (pintype "passive"))
      (node (ref "C31") (pin "1") (pinfunction "1_1") (pintype "passive"))
      (node (ref "C32") (pin "1") (pinfunction "1_1") (pintype "passive"))
      (node (ref "C33") (pin "1") (pinfunction "1_1") (pintype "passive"))
      (node (ref "C34") (pin "1") (pinfunction "1_1") (pintype "passive"))
      (node (ref "C35") (pin "1") (pinfunction "1_1") (pintype "passive"))
      (node (ref "C36") (pin "1") (pinfunction "1_1") (pintype "passive"))
      (node (ref "C38") (pin "+") (pinfunction "+_+") (pintype "passive"))
      (node (ref "C39") (pin "+") (pinfunction "+_+") (pintype "passive"))
      (node (ref "C4") (pin "1") (pinfunction "1_1") (pintype "passive"))
      (node (ref "C5") (pin "1") (pinfunction "1_1") (pintype "passive"))
      (node (ref "C6") (pin "1") (pinfunction "1_1") (pintype "passive"))
      (node (ref "C7") (pin "1") (pinfunction "1_1") (pintype "passive"))
      (node (ref "C8") (pin "1") (pinfunction "1_1") (pintype "passive"))
      (node (ref "C9") (pin "1") (pinfunction "1_1") (pintype "passive"))
      (node (ref "E16") (pin "10") (pinfunction "PRE_10") (pintype "input"))
      (node (ref "E16") (pin "4") (pinfunction "PRE_4") (pintype "input"))
      (node (ref "E20") (pin "10") (pinfunction "PRE_10") (pintype "input"))
      (node (ref "E29") (pin "6") (pinfunction "G1_6") (pintype "input"))
      (node (ref "E34") (pin "10") (pinfunction "1A4_10") (pintype "input"))
      (node (ref "E35") (pin "6") (pinfunction "G1_6") (pintype "input"))
      (node (ref "E36") (pin "1") (pinfunction "CLR_1") (pintype "input"))
      (node (ref "E36") (pin "11") (pinfunction "D4_11") (pintype "input"))
      (node (ref "E36") (pin "13") (pinfunction "D5_13") (pintype "input"))
      (node (ref "E36") (pin "6") (pinfunction "D3_6") (pintype "input"))
      (node (ref "E4") (pin "10") (pinfunction "B_10") (pintype "input"))
      (node (ref "E4") (pin "11") (pinfunction "CLR_11") (pintype "input"))
      (node (ref "J1") (pin "1") (pinfunction "1_1") (pintype "passive"))
      (node (ref "J1") (pin "2") (pinfunction "2_2") (pintype "passive"))
      (node (ref "J1") (pin "3") (pinfunction "3_3") (pintype "passive"))
      (node (ref "J1") (pin "4") (pinfunction "4_4") (pintype "passive"))
      (node (ref "J1") (pin "5") (pinfunction "5_5") (pintype "passive"))
      (node (ref "J1") (pin "7") (pinfunction "7_7") (pintype "passive"))
      (node (ref "J1") (pin "9") (pinfunction "9_9") (pintype "passive"))
      (node (ref "J2") (pin "1") (pinfunction "1_1") (pintype "passive"))
      (node (ref "J2") (pin "3") (pinfunction "3_3") (pintype "passive"))
      (node (ref "J2") (pin "5") (pinfunction "5_5") (pintype "passive"))
      (node (ref "J2") (pin "7") (pinfunction "7_7") (pintype "passive"))
      (node (ref "J2") (pin "9") (pinfunction "9_9") (pintype "passive"))
      (node (ref "J3") (pin "16") (pinfunction "16_16") (pintype "passive"))
      (node (ref "J4") (pin "16") (pinfunction "16_16") (pintype "passive"))
      (node (ref "R10") (pin "2") (pinfunction "2_2") (pintype "passive"))
      (node (ref "R11") (pin "2") (pinfunction "2_2") (pintype "passive"))
      (node (ref "R12") (pin "2") (pinfunction "2_2") (pintype "passive"))
      (node (ref "R13") (pin "2") (pinfunction "2_2") (pintype "passive"))
      (node (ref "R14") (pin "2") (pinfunction "2_2") (pintype "passive"))
      (node (ref "R15") (pin "2") (pinfunction "2_2") (pintype "passive"))
      (node (ref "R16") (pin "2") (pinfunction "2_2") (pintype "passive"))
      (node (ref "R25") (pin "1") (pinfunction "1_1") (pintype "passive"))
      (node (ref "R26") (pin "2") (pinfunction "2_2") (pintype "passive"))
      (node (ref "R28") (pin "2") (pinfunction "2_2") (pintype "passive"))
      (node (ref "R29") (pin "2") (pinfunction "2_2") (pintype "passive"))
      (node (ref "R31") (pin "2") (pinfunction "2_2") (pintype "passive"))
      (node (ref "R32") (pin "2") (pinfunction "2_2") (pintype "passive"))
      (node (ref "R33") (pin "2") (pinfunction "2_2") (pintype "passive"))
      (node (ref "R34") (pin "1") (pinfunction "1_1") (pintype "passive"))
      (node (ref "R35") (pin "1") (pinfunction "1_1") (pintype "passive"))
      (node (ref "R36") (pin "1") (pinfunction "1_1") (pintype "passive"))
      (node (ref "R37") (pin "2") (pinfunction "2_2") (pintype "passive"))
      (node (ref "R5") (pin "2") (pinfunction "2_2") (pintype "passive"))
      (node (ref "R6") (pin "2") (pinfunction "2_2") (pintype "passive"))
      (node (ref "R7") (pin "2") (pinfunction "2_2") (pintype "passive"))
      (node (ref "R8") (pin "2") (pinfunction "2_2") (pintype "passive"))
      (node (ref "R9") (pin "2") (pinfunction "2_2") (pintype "passive"))
      (node (ref "VCC") (pin "1") (pinfunction "P_1") (pintype "passive"))
    )
    (net (code "136") (name "unconnected-(E4B-~{Q}-Pad12)") (class "Default")
      (node (ref "E4") (pin "12") (pinfunction "~{Q}_12") (pintype "output"))
    )
    (net (code "137") (name "unconnected-(E5A-~{Q1}-Pad3)") (class "Default")
      (node (ref "E5") (pin "3") (pinfunction "~{Q1}_3") (pintype "output"))
    )
    (net (code "138") (name "unconnected-(E5A-~{Q2}-Pad6)") (class "Default")
      (node (ref "E5") (pin "6") (pinfunction "~{Q2}_6") (pintype "output"))
    )
    (net (code "139") (name "unconnected-(E5A-~{Q3}-Pad11)") (class "Default")
      (node (ref "E5") (pin "11") (pinfunction "~{Q3}_11") (pintype "output"))
    )
    (net (code "140") (name "unconnected-(E5A-~{Q4}-Pad14)") (class "Default")
      (node (ref "E5") (pin "14") (pinfunction "~{Q4}_14") (pintype "output"))
    )
    (net (code "141") (name "unconnected-(E6A-~{Q1}-Pad3)") (class "Default")
      (node (ref "E6") (pin "3") (pinfunction "~{Q1}_3") (pintype "output"))
    )
    (net (code "142") (name "unconnected-(E6A-~{Q2}-Pad6)") (class "Default")
      (node (ref "E6") (pin "6") (pinfunction "~{Q2}_6") (pintype "output"))
    )
    (net (code "143") (name "unconnected-(E6A-~{Q3}-Pad11)") (class "Default")
      (node (ref "E6") (pin "11") (pinfunction "~{Q3}_11") (pintype "output"))
    )
    (net (code "144") (name "unconnected-(E6A-~{Q4}-Pad14)") (class "Default")
      (node (ref "E6") (pin "14") (pinfunction "~{Q4}_14") (pintype "output"))
    )
    (net (code "145") (name "unconnected-(E7A-~{Q1}-Pad3)") (class "Default")
      (node (ref "E7") (pin "3") (pinfunction "~{Q1}_3") (pintype "output"))
    )
    (net (code "146") (name "unconnected-(E7A-~{Q2}-Pad6)") (class "Default")
      (node (ref "E7") (pin "6") (pinfunction "~{Q2}_6") (pintype "output"))
    )
    (net (code "147") (name "unconnected-(E7A-~{Q3}-Pad11)") (class "Default")
      (node (ref "E7") (pin "11") (pinfunction "~{Q3}_11") (pintype "output"))
    )
    (net (code "148") (name "unconnected-(E7A-~{Q4}-Pad14)") (class "Default")
      (node (ref "E7") (pin "14") (pinfunction "~{Q4}_14") (pintype "output"))
    )
    (net (code "149") (name "unconnected-(E16A-Q-Pad5)") (class "Default")
      (node (ref "E16") (pin "5") (pinfunction "Q_5") (pintype "output"))
    )
    (net (code "150") (name "unconnected-(E20A-~{Q}-Pad6)") (class "Default")
      (node (ref "E20") (pin "6") (pinfunction "~{Q}_6") (pintype "output"))
    )
    (net (code "151") (name "unconnected-(E26A-~{Q1}-Pad1)") (class "Default")
      (node (ref "E26") (pin "1") (pinfunction "~{Q1}_1") (pintype "output"))
    )
    (net (code "152") (name "unconnected-(E26A-~{Q2}-Pad14)") (class "Default")
      (node (ref "E26") (pin "14") (pinfunction "~{Q2}_14") (pintype "output"))
    )
    (net (code "153") (name "unconnected-(E26A-~{Q3}-Pad11)") (class "Default")
      (node (ref "E26") (pin "11") (pinfunction "~{Q3}_11") (pintype "output"))
    )
    (net (code "154") (name "unconnected-(E34A-1Y4-Pad9)") (class "Default")
      (node (ref "E34") (pin "9") (pinfunction "1Y4_9") (pintype "tri_state"))
    )
    (net (code "155") (name "unconnected-(E35A-Y0-Pad15)") (class "Default")
      (node (ref "E35") (pin "15") (pinfunction "Y0_15") (pintype "output"))
    )
    (net (code "156") (name "unconnected-(E35A-Y1-Pad14)") (class "Default")
      (node (ref "E35") (pin "14") (pinfunction "Y1_14") (pintype "output"))
    )
    (net (code "157") (name "unconnected-(E35A-Y2-Pad13)") (class "Default")
      (node (ref "E35") (pin "13") (pinfunction "Y2_13") (pintype "output"))
    )
    (net (code "158") (name "unconnected-(E35A-Y3-Pad12)") (class "Default")
      (node (ref "E35") (pin "12") (pinfunction "Y3_12") (pintype "output"))
    )
    (net (code "159") (name "unconnected-(E35A-Y7-Pad7)") (class "Default")
      (node (ref "E35") (pin "7") (pinfunction "Y7_7") (pintype "output"))
    )
    (net (code "160") (name "unconnected-(E36A-Q3-Pad7)") (class "Default")
      (node (ref "E36") (pin "7") (pinfunction "Q3_7") (pintype "output"))
    )
    (net (code "161") (name "unconnected-(E36A-Q4-Pad10)") (class "Default")
      (node (ref "E36") (pin "10") (pinfunction "Q4_10") (pintype "output"))
    )
    (net (code "162") (name "unconnected-(E36A-Q5-Pad12)") (class "Default")
      (node (ref "E36") (pin "12") (pinfunction "Q5_12") (pintype "output"))
    )
    (net (code "163") (name "~{ADRLTH}") (class "Default")
      (node (ref "E12") (pin "9") (pinfunction "CLK_9") (pintype "input"))
      (node (ref "E14") (pin "9") (pinfunction "CLK_9") (pintype "input"))
      (node (ref "E8") (pin "11") (pinfunction "O_11") (pintype "output"))
    )
    (net (code "164") (name "~{BFSW}") (class "Default")
      (node (ref "E28") (pin "9") (pinfunction "1Y4_9") (pintype "tri_state"))
      (node (ref "J2") (pin "24") (pinfunction "24_24") (pintype "passive"))
    )
    (net (code "165") (name "~{BKDTACNTL}") (class "Default")
      (node (ref "E28") (pin "3") (pinfunction "1Y1_3") (pintype "tri_state"))
      (node (ref "J2") (pin "12") (pinfunction "12_12") (pintype "passive"))
    )
    (net (code "166") (name "~{BOOTF}") (class "Default")
      (node (ref "E16") (pin "2") (pinfunction "D_2") (pintype "input"))
      (node (ref "E16") (pin "6") (pinfunction "~{Q}_6") (pintype "output"))
      (node (ref "E28") (pin "10") (pinfunction "1A4_10") (pintype "input"))
    )
    (net (code "167") (name "~{BUSEN}") (class "Default")
      (node (ref "E34") (pin "13") (pinfunction "2Y2_13") (pintype "tri_state"))
      (node (ref "J1") (pin "24") (pinfunction "24_24") (pintype "passive"))
    )
    (net (code "168") (name "~{DEP}") (class "Default")
      (node (ref "E28") (pin "5") (pinfunction "1Y2_5") (pintype "tri_state"))
      (node (ref "J2") (pin "20") (pinfunction "20_20") (pintype "passive"))
    )
    (net (code "169") (name "~{DSPLTH}") (class "Default")
      (node (ref "E13") (pin "9") (pinfunction "CLK_9") (pintype "input"))
      (node (ref "E15") (pin "9") (pinfunction "CLK_9") (pintype "input"))
      (node (ref "E8") (pin "8") (pinfunction "O_8") (pintype "output"))
    )
    (net (code "170") (name "~{EMA0}") (class "Default")
      (node (ref "E27") (pin "11") (pinfunction "I_11") (pintype "input"))
      (node (ref "J1") (pin "30") (pinfunction "30_30") (pintype "passive"))
      (node (ref "R34") (pin "2") (pinfunction "2_2") (pintype "passive"))
    )
    (net (code "171") (name "~{EMA1}") (class "Default")
      (node (ref "E27") (pin "9") (pinfunction "I_9") (pintype "input"))
      (node (ref "J1") (pin "28") (pinfunction "28_28") (pintype "passive"))
      (node (ref "R35") (pin "2") (pinfunction "2_2") (pintype "passive"))
    )
    (net (code "172") (name "~{EMA2}") (class "Default")
      (node (ref "E27") (pin "13") (pinfunction "I_13") (pintype "input"))
      (node (ref "J1") (pin "32") (pinfunction "32_32") (pintype "passive"))
      (node (ref "R36") (pin "2") (pinfunction "2_2") (pintype "passive"))
    )
    (net (code "173") (name "~{EMODE}") (class "Default")
      (node (ref "E1") (pin "6") (pinfunction "MOD_6") (pintype "input"))
      (node (ref "E16") (pin "8") (pinfunction "~{Q}_8") (pintype "output"))
      (node (ref "E2") (pin "6") (pinfunction "MOD_6") (pintype "input"))
      (node (ref "E22") (pin "6") (pinfunction "I1_6") (pintype "input"))
      (node (ref "E3") (pin "6") (pinfunction "MOD_6") (pintype "input"))
    )
    (net (code "174") (name "~{EXTPUL}") (class "Default")
      (node (ref "J4") (pin "9") (pinfunction "9_9") (pintype "passive"))
    )
    (net (code "175") (name "~{FUN}") (class "Default")
      (node (ref "E24") (pin "3") (pinfunction "I_3") (pintype "input"))
      (node (ref "E25") (pin "11") (pinfunction "I2_11") (pintype "input"))
      (node (ref "E25") (pin "2") (pinfunction "I1_2") (pintype "input"))
      (node (ref "J4") (pin "15") (pinfunction "15_15") (pintype "passive"))
    )
    (net (code "176") (name "~{GATEENT}") (class "Default")
      (node (ref "E10") (pin "1") (pinfunction "G_1") (pintype "input"))
      (node (ref "E11") (pin "1") (pinfunction "G_1") (pintype "input"))
      (node (ref "E21") (pin "6") (pinfunction "O_6") (pintype "output"))
      (node (ref "E30") (pin "5") (pinfunction "I1_5") (pintype "input"))
      (node (ref "E9") (pin "1") (pinfunction "G_1") (pintype "input"))
    )
    (net (code "177") (name "~{GATESR}") (class "Default")
      (node (ref "E10") (pin "19") (pinfunction "G_19") (pintype "input"))
      (node (ref "E11") (pin "19") (pinfunction "G_19") (pintype "input"))
      (node (ref "E32") (pin "11") (pinfunction "O_11") (pintype "output"))
      (node (ref "E9") (pin "19") (pinfunction "G_19") (pintype "input"))
    )
    (net (code "178") (name "~{IND1}") (class "Default")
      (node (ref "E28") (pin "7") (pinfunction "1Y3_7") (pintype "tri_state"))
      (node (ref "E34") (pin "3") (pinfunction "1Y1_3") (pintype "tri_state"))
      (node (ref "J2") (pin "8") (pinfunction "8_8") (pintype "passive"))
    )
    (net (code "179") (name "~{IND2}") (class "Default")
      (node (ref "E34") (pin "5") (pinfunction "1Y2_5") (pintype "tri_state"))
      (node (ref "J2") (pin "4") (pinfunction "4_4") (pintype "passive"))
    )
    (net (code "180") (name "~{INIT}") (class "Default")
      (node (ref "E31") (pin "9") (pinfunction "1Y4_9") (pintype "tri_state"))
      (node (ref "J2") (pin "34") (pinfunction "34_34") (pintype "passive"))
    )
    (net (code "181") (name "~{KEY-F}") (class "Default")
      (node (ref "E26") (pin "13") (pinfunction "C12_13") (pintype "input"))
      (node (ref "E26") (pin "4") (pinfunction "C34_4") (pintype "input"))
      (node (ref "E27") (pin "5") (pinfunction "I_5") (pintype "input"))
      (node (ref "J4") (pin "3") (pinfunction "3_3") (pintype "passive"))
    )
    (net (code "182") (name "~{KEYCNTL}") (class "Default")
      (node (ref "E31") (pin "13") (pinfunction "2Y2_13") (pintype "tri_state"))
      (node (ref "J2") (pin "10") (pinfunction "10_10") (pintype "passive"))
    )
    (net (code "183") (name "~{KEYSTB}") (class "Default")
      (node (ref "E16") (pin "11") (pinfunction "CLK_11") (pintype "input"))
      (node (ref "E21") (pin "2") (pinfunction "I1_2") (pintype "input"))
      (node (ref "E24") (pin "2") (pinfunction "O_2") (pintype "output"))
      (node (ref "E31") (pin "1") (pinfunction "1G_1") (pintype "input"))
      (node (ref "E33") (pin "11") (pinfunction "I0_11") (pintype "input"))
      (node (ref "E33") (pin "9") (pinfunction "I1_9") (pintype "input"))
    )
    (net (code "184") (name "~{KFUN0}") (class "Default")
      (node (ref "E26") (pin "2") (pinfunction "D1_2") (pintype "input"))
      (node (ref "E3") (pin "1") (pinfunction "SER_1") (pintype "input"))
      (node (ref "E3") (pin "2") (pinfunction "A_2") (pintype "input"))
      (node (ref "J3") (pin "3") (pinfunction "3_3") (pintype "passive"))
    )
    (net (code "185") (name "~{KFUN1}") (class "Default")
      (node (ref "E2") (pin "1") (pinfunction "SER_1") (pintype "input"))
      (node (ref "E2") (pin "2") (pinfunction "A_2") (pintype "input"))
      (node (ref "E26") (pin "3") (pinfunction "D2_3") (pintype "input"))
      (node (ref "J3") (pin "2") (pinfunction "2_2") (pintype "passive"))
    )
    (net (code "186") (name "~{KFUN2}") (class "Default")
      (node (ref "E1") (pin "1") (pinfunction "SER_1") (pintype "input"))
      (node (ref "E1") (pin "2") (pinfunction "A_2") (pintype "input"))
      (node (ref "E26") (pin "6") (pinfunction "D3_6") (pintype "input"))
      (node (ref "J3") (pin "1") (pinfunction "1_1") (pintype "passive"))
    )
    (net (code "187") (name "~{LAENAB}") (class "Default")
      (node (ref "E23") (pin "2") (pinfunction "O_2") (pintype "open_collector"))
      (node (ref "J2") (pin "22") (pinfunction "22_22") (pintype "passive"))
    )
    (net (code "188") (name "~{MAEN}") (class "Default")
      (node (ref "E23") (pin "8") (pinfunction "O_8") (pintype "open_collector"))
      (node (ref "J2") (pin "32") (pinfunction "32_32") (pintype "passive"))
    )
    (net (code "189") (name "~{MALC}") (class "Default")
      (node (ref "E28") (pin "11") (pinfunction "2Y1_11") (pintype "tri_state"))
      (node (ref "J2") (pin "36") (pinfunction "36_36") (pintype "passive"))
    )
    (net (code "190") (name "~{MCLOCK}") (class "Default")
      (node (ref "E33") (pin "2") (pinfunction "I0_2") (pintype "input"))
      (node (ref "J4") (pin "1") (pinfunction "1_1") (pintype "passive"))
    )
    (net (code "191") (name "~{MD}") (class "Default")
      (node (ref "E34") (pin "7") (pinfunction "1Y3_7") (pintype "tri_state"))
      (node (ref "J2") (pin "18") (pinfunction "18_18") (pintype "passive"))
    )
    (net (code "192") (name "~{MEMSTART}") (class "Default")
      (node (ref "E23") (pin "12") (pinfunction "O_12") (pintype "open_collector"))
      (node (ref "J2") (pin "26") (pinfunction "26_26") (pintype "passive"))
    )
    (net (code "193") (name "~{MH0}") (class "Default")
      (node (ref "E20") (pin "12") (pinfunction "D_12") (pintype "input"))
      (node (ref "E20") (pin "8") (pinfunction "~{Q}_8") (pintype "output"))
      (node (ref "E21") (pin "9") (pinfunction "I0_9") (pintype "input"))
      (node (ref "E8") (pin "2") (pinfunction "I1_2") (pintype "input"))
      (node (ref "E8") (pin "9") (pinfunction "I0_9") (pintype "input"))
    )
    (net (code "194") (name "~{MSIRDIS}") (class "Default")
      (node (ref "E31") (pin "11") (pinfunction "2Y1_11") (pintype "tri_state"))
      (node (ref "J2") (pin "2") (pinfunction "2_2") (pintype "passive"))
    )
    (net (code "195") (name "~{PANLOCK}") (class "Default")
      (node (ref "E24") (pin "13") (pinfunction "I_13") (pintype "input"))
      (node (ref "J2") (pin "6") (pinfunction "6_6") (pintype "passive"))
      (node (ref "R31") (pin "1") (pinfunction "1_1") (pintype "passive"))
    )
    (net (code "196") (name "~{PULSELOADADD}") (class "Default")
      (node (ref "E31") (pin "7") (pinfunction "1Y3_7") (pintype "tri_state"))
      (node (ref "J2") (pin "40") (pinfunction "40_40") (pintype "passive"))
    )
    (net (code "197") (name "~{RUN}") (class "Default")
      (node (ref "E24") (pin "5") (pinfunction "I_5") (pintype "input"))
      (node (ref "J1") (pin "18") (pinfunction "18_18") (pintype "passive"))
      (node (ref "R28") (pin "1") (pinfunction "1_1") (pintype "passive"))
    )
    (net (code "198") (name "~{SHLT}") (class "Default")
      (node (ref "E27") (pin "1") (pinfunction "I_1") (pintype "input"))
      (node (ref "J3") (pin "5") (pinfunction "5_5") (pintype "passive"))
    )
    (net (code "199") (name "~{SINGSTEP}") (class "Default")
      (node (ref "E28") (pin "13") (pinfunction "2Y2_13") (pintype "tri_state"))
      (node (ref "J2") (pin "14") (pinfunction "14_14") (pintype "passive"))
    )
    (net (code "200") (name "~{SRDATA}") (class "Default")
      (node (ref "E32") (pin "13") (pinfunction "I1_13") (pintype "input"))
      (node (ref "E8") (pin "1") (pinfunction "I0_1") (pintype "input"))
      (node (ref "J2") (pin "30") (pinfunction "30_30") (pintype "passive"))
      (node (ref "R29") (pin "1") (pinfunction "1_1") (pintype "passive"))
      (node (ref "R30") (pin "2") (pinfunction "2_2") (pintype "passive"))
    )
    (net (code "201") (name "~{STATE}") (class "Default")
      (node (ref "E34") (pin "11") (pinfunction "2Y1_11") (pintype "tri_state"))
      (node (ref "J2") (pin "38") (pinfunction "38_38") (pintype "passive"))
    )
    (net (code "202") (name "~{STHIS}") (class "Default")
      (node (ref "E20") (pin "2") (pinfunction "D_2") (pintype "input"))
      (node (ref "J3") (pin "4") (pinfunction "4_4") (pintype "passive"))
    )
    (net (code "203") (name "~{TS1}") (class "Default")
      (node (ref "E20") (pin "3") (pinfunction "CLK_3") (pintype "input"))
      (node (ref "E21") (pin "10") (pinfunction "I1_10") (pintype "input"))
      (node (ref "E24") (pin "9") (pinfunction "I_9") (pintype "input"))
      (node (ref "J1") (pin "26") (pinfunction "26_26") (pintype "passive"))
      (node (ref "R26") (pin "1") (pinfunction "1_1") (pintype "passive"))
      (node (ref "R27") (pin "2") (pinfunction "2_2") (pintype "passive"))
    )
  )
)
